# ouch_area_schematic.net
KiCad netlist of a schematic drawn in Altium Designer
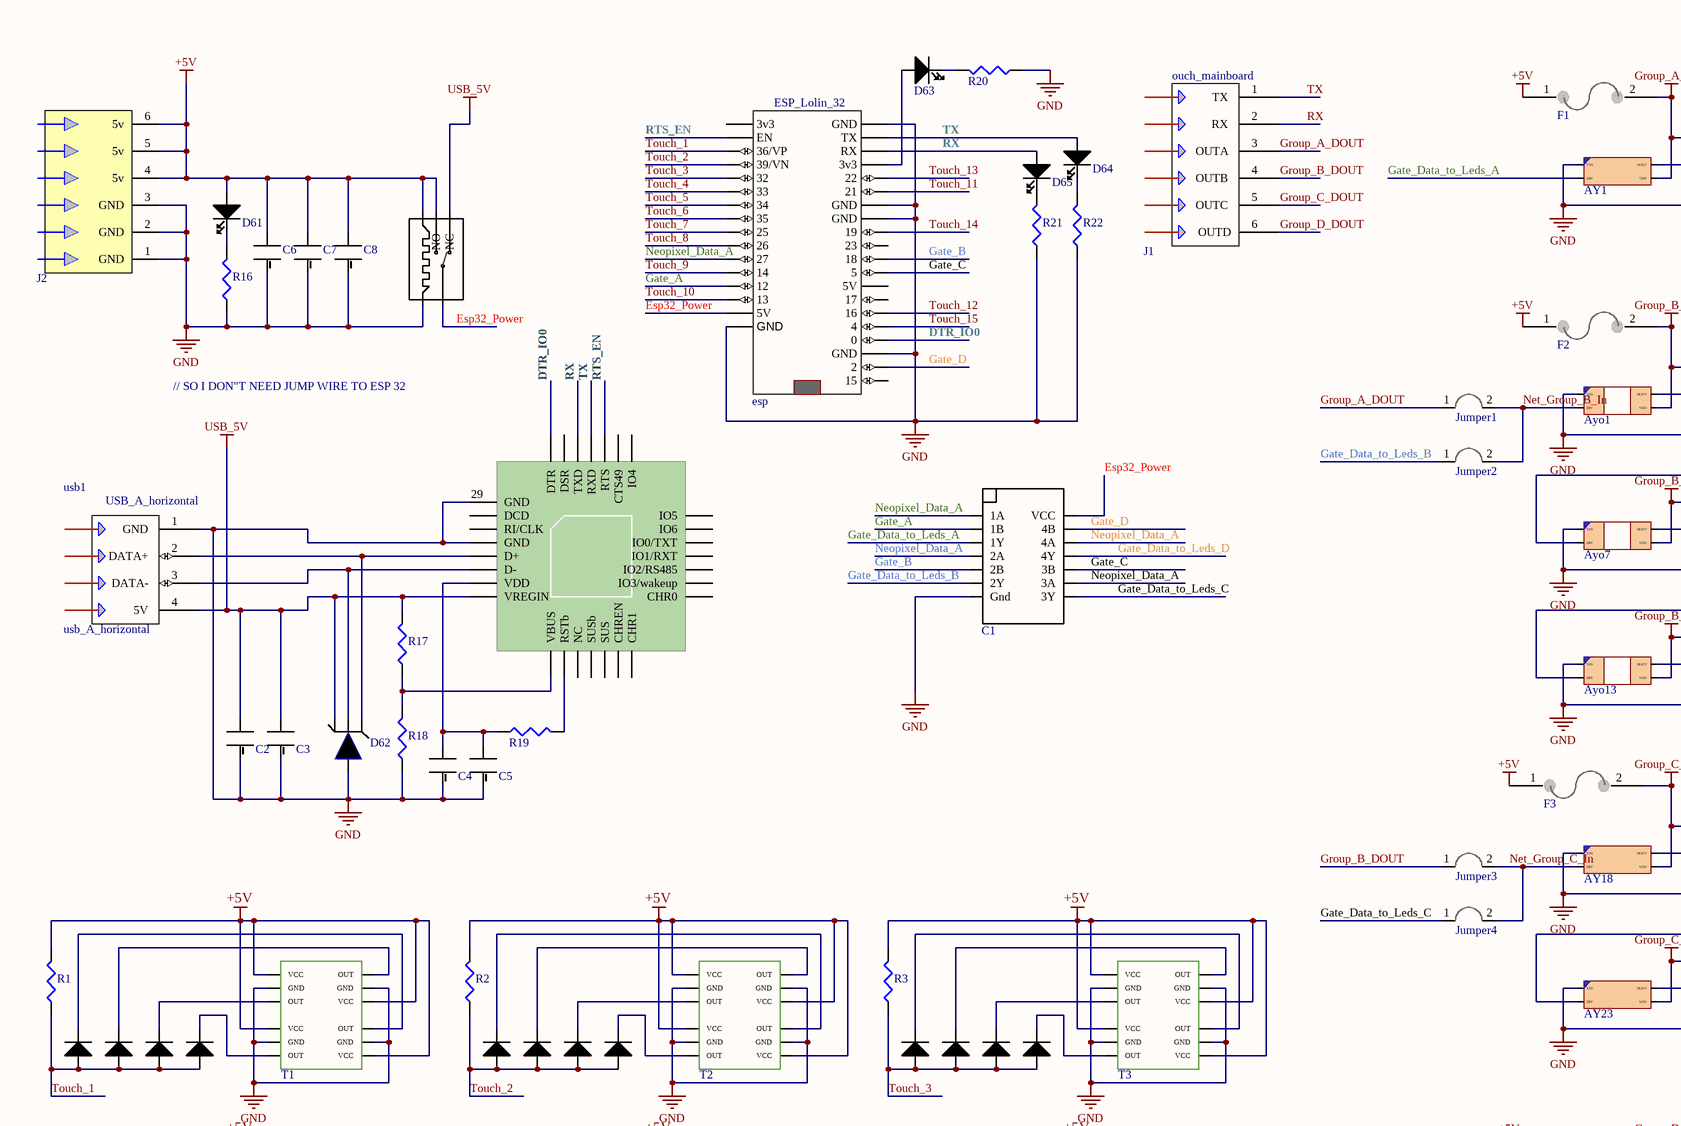
[diagram p0: ouch_area_schematic.SchDoc, top left]
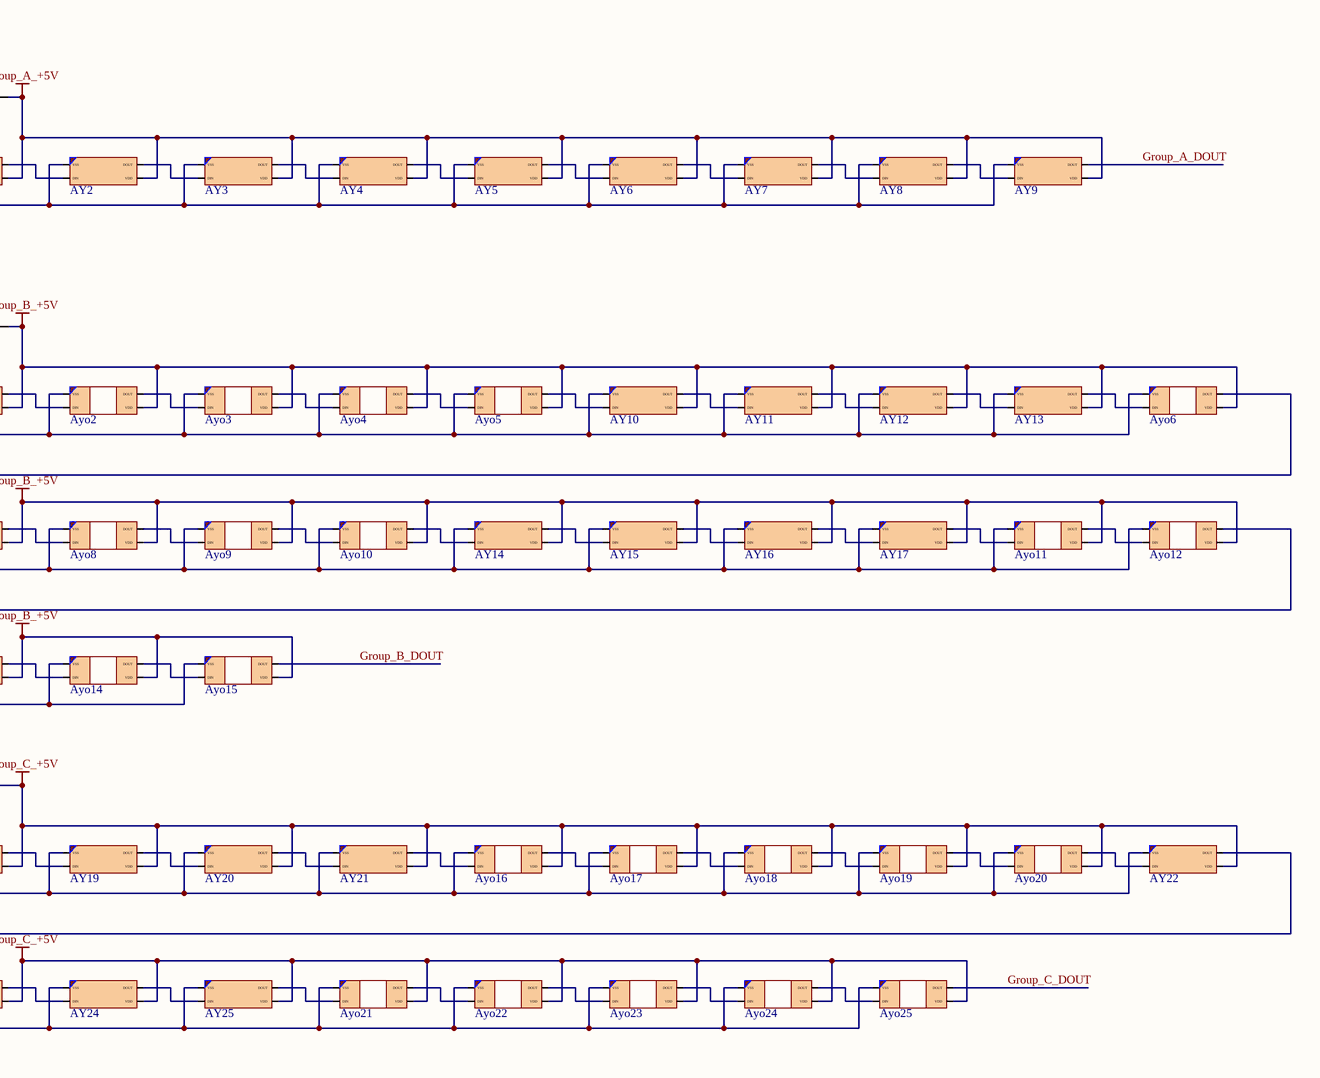
[diagram p1: ouch_area_schematic.SchDoc, top right]
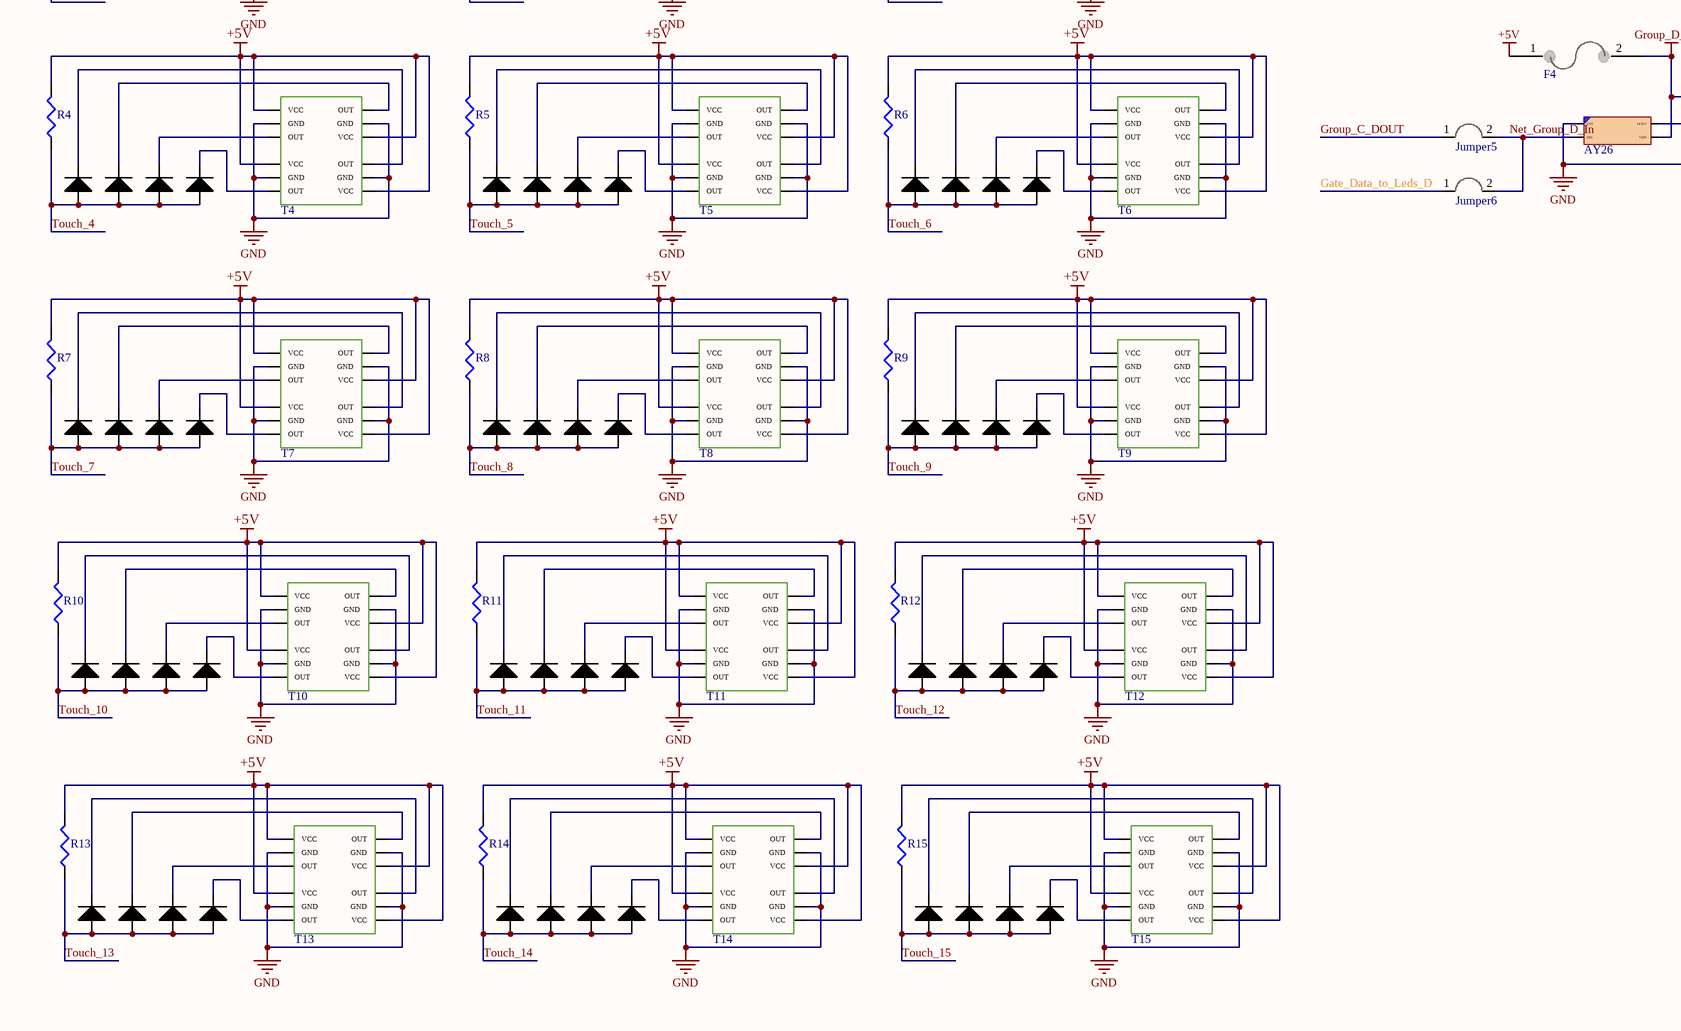
[diagram p2: ouch_area_schematic.SchDoc, bottom left]
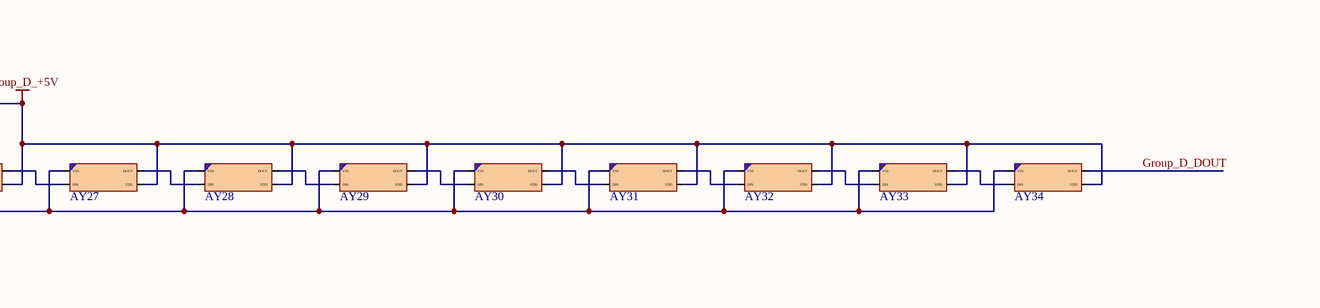
[diagram p3: ouch_area_schematic.SchDoc, bottom right]

(export (version "E")
  (design (tool "Eeschema 10.0.6"))
  (components
    (comp (ref "AY1")
      (value "1")
      (footprint "27xWs2812B_withC")
      (libsource (lib "WTFschlibra") (part "Ws2812_27leds"))
    )
    (comp (ref "AY2")
      (value "28")
      (footprint "27xWs2812B_withC")
      (libsource (lib "WTFschlibra") (part "Ws2812_27leds"))
    )
    (comp (ref "AY3")
      (value "55")
      (footprint "27xWs2812B_withC")
      (libsource (lib "WTFschlibra") (part "Ws2812_27leds"))
    )
    (comp (ref "AY4")
      (value "82")
      (footprint "27xWs2812B_withC")
      (libsource (lib "WTFschlibra") (part "Ws2812_27leds"))
    )
    (comp (ref "AY5")
      (value "109")
      (footprint "27xWs2812B_withC")
      (libsource (lib "WTFschlibra") (part "Ws2812_27leds"))
    )
    (comp (ref "AY6")
      (value "136")
      (footprint "27xWs2812B_withC")
      (libsource (lib "WTFschlibra") (part "Ws2812_27leds"))
    )
    (comp (ref "AY7")
      (value "163")
      (footprint "27xWs2812B_withC")
      (libsource (lib "WTFschlibra") (part "Ws2812_27leds"))
    )
    (comp (ref "AY8")
      (value "190")
      (footprint "27xWs2812B_withC")
      (libsource (lib "WTFschlibra") (part "Ws2812_27leds"))
    )
    (comp (ref "AY9")
      (value "217")
      (footprint "27xWs2812B_withC")
      (libsource (lib "WTFschlibra") (part "Ws2812_27leds"))
    )
    (comp (ref "AY10")
      (value "304")
      (footprint "27xWs2812B_withC")
      (libsource (lib "WTFschlibra") (part "Ws2812_27leds"))
    )
    (comp (ref "AY11")
      (value "331")
      (footprint "27xWs2812B_withC")
      (libsource (lib "WTFschlibra") (part "Ws2812_27leds"))
    )
    (comp (ref "AY12")
      (value "358")
      (footprint "27xWs2812B_withC")
      (libsource (lib "WTFschlibra") (part "Ws2812_27leds"))
    )
    (comp (ref "AY13")
      (value "385")
      (footprint "27xWs2812B_withC")
      (libsource (lib "WTFschlibra") (part "Ws2812_27leds"))
    )
    (comp (ref "AY14")
      (value "472")
      (footprint "27xWs2812B_withC")
      (libsource (lib "WTFschlibra") (part "Ws2812_27leds"))
    )
    (comp (ref "AY15")
      (value "499")
      (footprint "27xWs2812B_withC")
      (libsource (lib "WTFschlibra") (part "Ws2812_27leds"))
    )
    (comp (ref "AY16")
      (value "526")
      (footprint "27xWs2812B_withC")
      (libsource (lib "WTFschlibra") (part "Ws2812_27leds"))
    )
    (comp (ref "AY17")
      (value "553")
      (footprint "27xWs2812B_withC")
      (libsource (lib "WTFschlibra") (part "Ws2812_27leds"))
    )
    (comp (ref "AY18")
      (value "640")
      (footprint "27xWs2812B_withC")
      (libsource (lib "WTFschlibra") (part "Ws2812_27leds"))
    )
    (comp (ref "AY19")
      (value "667")
      (footprint "27xWs2812B_withC")
      (libsource (lib "WTFschlibra") (part "Ws2812_27leds"))
    )
    (comp (ref "AY20")
      (value "694")
      (footprint "27xWs2812B_withC")
      (libsource (lib "WTFschlibra") (part "Ws2812_27leds"))
    )
    (comp (ref "AY21")
      (value "721")
      (footprint "27xWs2812B_withC")
      (libsource (lib "WTFschlibra") (part "Ws2812_27leds"))
    )
    (comp (ref "AY22")
      (value "808")
      (footprint "27xWs2812B_withC")
      (libsource (lib "WTFschlibra") (part "Ws2812_27leds"))
    )
    (comp (ref "AY23")
      (value "835")
      (footprint "27xWs2812B_withC")
      (libsource (lib "WTFschlibra") (part "Ws2812_27leds"))
    )
    (comp (ref "AY24")
      (value "862")
      (footprint "27xWs2812B_withC")
      (libsource (lib "WTFschlibra") (part "Ws2812_27leds"))
    )
    (comp (ref "AY25")
      (value "889")
      (footprint "27xWs2812B_withC")
      (libsource (lib "WTFschlibra") (part "Ws2812_27leds"))
    )
    (comp (ref "AY26")
      (value "976")
      (footprint "27xWs2812B_withC")
      (libsource (lib "WTFschlibra") (part "Ws2812_27leds"))
    )
    (comp (ref "AY27")
      (value "1003")
      (footprint "27xWs2812B_withC")
      (libsource (lib "WTFschlibra") (part "Ws2812_27leds"))
    )
    (comp (ref "AY28")
      (value "1030")
      (footprint "27xWs2812B_withC")
      (libsource (lib "WTFschlibra") (part "Ws2812_27leds"))
    )
    (comp (ref "AY29")
      (value "1057")
      (footprint "27xWs2812B_withC")
      (libsource (lib "WTFschlibra") (part "Ws2812_27leds"))
    )
    (comp (ref "AY30")
      (value "1084")
      (footprint "27xWs2812B_withC")
      (libsource (lib "WTFschlibra") (part "Ws2812_27leds"))
    )
    (comp (ref "AY31")
      (value "1111")
      (footprint "27xWs2812B_withC")
      (libsource (lib "WTFschlibra") (part "Ws2812_27leds"))
    )
    (comp (ref "AY32")
      (value "1138")
      (footprint "27xWs2812B_withC")
      (libsource (lib "WTFschlibra") (part "Ws2812_27leds"))
    )
    (comp (ref "AY33")
      (value "1165")
      (footprint "27xWs2812B_withC")
      (libsource (lib "WTFschlibra") (part "Ws2812_27leds"))
    )
    (comp (ref "AY34")
      (value "1192")
      (footprint "27xWs2812B_withC")
      (libsource (lib "WTFschlibra") (part "Ws2812_27leds"))
    )
    (comp (ref "Ayo1")
      (value "244")
      (footprint "12Xws2812b_owo")
      (libsource (lib "WTFschlibra") (part "Ws2812_12ledsOwO"))
    )
    (comp (ref "Ayo2")
      (value "256")
      (footprint "12Xws2812b_owo")
      (libsource (lib "WTFschlibra") (part "Ws2812_12ledsOwO"))
    )
    (comp (ref "Ayo3")
      (value "268")
      (footprint "12Xws2812b_owo")
      (libsource (lib "WTFschlibra") (part "Ws2812_12ledsOwO"))
    )
    (comp (ref "Ayo4")
      (value "280")
      (footprint "12Xws2812b_owo")
      (libsource (lib "WTFschlibra") (part "Ws2812_12ledsOwO"))
    )
    (comp (ref "Ayo5")
      (value "292")
      (footprint "12Xws2812b_owo")
      (libsource (lib "WTFschlibra") (part "Ws2812_12ledsOwO"))
    )
    (comp (ref "Ayo6")
      (value "412")
      (footprint "12Xws2812b_owo")
      (libsource (lib "WTFschlibra") (part "Ws2812_12ledsOwO"))
    )
    (comp (ref "Ayo7")
      (value "424")
      (footprint "12Xws2812b_owo")
      (libsource (lib "WTFschlibra") (part "Ws2812_12ledsOwO"))
    )
    (comp (ref "Ayo8")
      (value "436")
      (footprint "12Xws2812b_owo")
      (libsource (lib "WTFschlibra") (part "Ws2812_12ledsOwO"))
    )
    (comp (ref "Ayo9")
      (value "448")
      (footprint "12Xws2812b_owo")
      (libsource (lib "WTFschlibra") (part "Ws2812_12ledsOwO"))
    )
    (comp (ref "Ayo10")
      (value "460")
      (footprint "12Xws2812b_owo")
      (libsource (lib "WTFschlibra") (part "Ws2812_12ledsOwO"))
    )
    (comp (ref "Ayo11")
      (value "580")
      (footprint "12Xws2812b_owo")
      (libsource (lib "WTFschlibra") (part "Ws2812_12ledsOwO"))
    )
    (comp (ref "Ayo12")
      (value "592")
      (footprint "12Xws2812b_owo")
      (libsource (lib "WTFschlibra") (part "Ws2812_12ledsOwO"))
    )
    (comp (ref "Ayo13")
      (value "604")
      (footprint "12Xws2812b_owo")
      (libsource (lib "WTFschlibra") (part "Ws2812_12ledsOwO"))
    )
    (comp (ref "Ayo14")
      (value "616")
      (footprint "12Xws2812b_owo")
      (libsource (lib "WTFschlibra") (part "Ws2812_12ledsOwO"))
    )
    (comp (ref "Ayo15")
      (value "628")
      (footprint "12Xws2812b_owo")
      (libsource (lib "WTFschlibra") (part "Ws2812_12ledsOwO"))
    )
    (comp (ref "Ayo16")
      (value "748")
      (footprint "12Xws2812b_owo")
      (libsource (lib "WTFschlibra") (part "Ws2812_12ledsOwO"))
    )
    (comp (ref "Ayo17")
      (value "760")
      (footprint "12Xws2812b_owo")
      (libsource (lib "WTFschlibra") (part "Ws2812_12ledsOwO"))
    )
    (comp (ref "Ayo18")
      (value "772")
      (footprint "12Xws2812b_owo")
      (libsource (lib "WTFschlibra") (part "Ws2812_12ledsOwO"))
    )
    (comp (ref "Ayo19")
      (value "784")
      (footprint "12Xws2812b_owo")
      (libsource (lib "WTFschlibra") (part "Ws2812_12ledsOwO"))
    )
    (comp (ref "Ayo20")
      (value "796")
      (footprint "12Xws2812b_owo")
      (libsource (lib "WTFschlibra") (part "Ws2812_12ledsOwO"))
    )
    (comp (ref "Ayo21")
      (value "916")
      (footprint "12Xws2812b_owo")
      (libsource (lib "WTFschlibra") (part "Ws2812_12ledsOwO"))
    )
    (comp (ref "Ayo22")
      (value "928")
      (footprint "12Xws2812b_owo")
      (libsource (lib "WTFschlibra") (part "Ws2812_12ledsOwO"))
    )
    (comp (ref "Ayo23")
      (value "940")
      (footprint "12Xws2812b_owo")
      (libsource (lib "WTFschlibra") (part "Ws2812_12ledsOwO"))
    )
    (comp (ref "Ayo24")
      (value "952")
      (footprint "12Xws2812b_owo")
      (libsource (lib "WTFschlibra") (part "Ws2812_12ledsOwO"))
    )
    (comp (ref "Ayo25")
      (value "964")
      (footprint "12Xws2812b_owo")
      (libsource (lib "WTFschlibra") (part "Ws2812_12ledsOwO"))
    )
    (comp (ref "C1")
      (value "74hc08d")
      (footprint "SOP14(74hc08d)")
      (libsource (lib "WTFschlibra") (part "74HC08"))
    )
    (comp (ref "C2")
      (value "C4R7")
      (footprint "Capacitor0603")
      (description "Cap Ceramic 4.7uF 6.3V X5R 20% Pad SMD 0402 85C T/R")
      (fields (field (name "TOLERANCE") "20%"))
      (libsource (lib "WTFschlibra") (part "capacitor0603"))
    )
    (comp (ref "C3")
      (value "C104")
      (footprint "Capacitor0603")
      (description "0.1uf")
      (fields (field (name "TOLERANCE") "20%"))
      (libsource (lib "WTFschlibra") (part "capacitor0603"))
    )
    (comp (ref "C4")
      (value "C104")
      (footprint "Capacitor0603")
      (description "4.7")
      (fields (field (name "TOLERANCE") "20%"))
      (libsource (lib "WTFschlibra") (part "capacitor0603"))
    )
    (comp (ref "C5")
      (value "C4R7")
      (footprint "Capacitor0603")
      (description "0.1")
      (fields (field (name "TOLERANCE") "20%"))
      (libsource (lib "WTFschlibra") (part "capacitor0603"))
    )
    (comp (ref "C6")
      (value "EEU-FM0J331")
      (footprint "2.5mmCapacitor")
      (description "Cap 330 uF;  Tol 20%;  Vol-Rtg 6.3 VDC;  Radial;  6.3x11.2;  Bulk")
      (fields (field (name "TOLERANCE") "20%") (field (name "VOLTAGE") "6.3V"))
      (libsource (lib "WTFschlibra") (part "EEU-FM0J331"))
    )
    (comp (ref "C7")
      (value "EEU-FM0J331")
      (footprint "2.5mmCapacitor")
      (description "Cap 330 uF;  Tol 20%;  Vol-Rtg 6.3 VDC;  Radial;  6.3x11.2;  Bulk")
      (fields (field (name "TOLERANCE") "20%") (field (name "VOLTAGE") "6.3V"))
      (libsource (lib "WTFschlibra") (part "EEU-FM0J331"))
    )
    (comp (ref "C8")
      (value "EEU-FM0J331")
      (footprint "2.5mmCapacitor")
      (description "Cap 330 uF;  Tol 20%;  Vol-Rtg 6.3 VDC;  Radial;  6.3x11.2;  Bulk")
      (fields (field (name "TOLERANCE") "20%") (field (name "VOLTAGE") "6.3V"))
      (libsource (lib "WTFschlibra") (part "EEU-FM0J331"))
    )
    (comp (ref "cp1")
      (value "CP2102N")
      (footprint "CP2102N_QFN28")
      (description "Full Speed USB to UART Bridge USB 2.0 3.3V T/R Automotive 28-Pin QFN EP")
      (libsource (lib "WTFschlibra") (part "CP2102N-A02-GQFN28R"))
    )
    (comp (ref "D1")
      (value "LL4148")
      (footprint "SOD80-LL4148")
      (description "ON SEMICONDUCTOR - LL4148 - Small Signal Diode, Single, 100 V, 200 mA, 1 V, 4 ns, 2 A")
      (fields (field (name "VOLTAGE") "100V"))
      (libsource (lib "WTFschlibra") (part "LL4148"))
    )
    (comp (ref "D2")
      (value "LL4148")
      (footprint "SOD80-LL4148")
      (description "ON SEMICONDUCTOR - LL4148 - Small Signal Diode, Single, 100 V, 200 mA, 1 V, 4 ns, 2 A")
      (fields (field (name "VOLTAGE") "100V"))
      (libsource (lib "WTFschlibra") (part "LL4148"))
    )
    (comp (ref "D3")
      (value "LL4148")
      (footprint "SOD80-LL4148")
      (description "ON SEMICONDUCTOR - LL4148 - Small Signal Diode, Single, 100 V, 200 mA, 1 V, 4 ns, 2 A")
      (fields (field (name "VOLTAGE") "100V"))
      (libsource (lib "WTFschlibra") (part "LL4148"))
    )
    (comp (ref "D4")
      (value "LL4148")
      (footprint "SOD80-LL4148")
      (description "ON SEMICONDUCTOR - LL4148 - Small Signal Diode, Single, 100 V, 200 mA, 1 V, 4 ns, 2 A")
      (fields (field (name "VOLTAGE") "100V"))
      (libsource (lib "WTFschlibra") (part "LL4148"))
    )
    (comp (ref "D5")
      (value "LL4148")
      (footprint "SOD80-LL4148")
      (description "ON SEMICONDUCTOR - LL4148 - Small Signal Diode, Single, 100 V, 200 mA, 1 V, 4 ns, 2 A")
      (fields (field (name "VOLTAGE") "100V"))
      (libsource (lib "WTFschlibra") (part "LL4148"))
    )
    (comp (ref "D6")
      (value "LL4148")
      (footprint "SOD80-LL4148")
      (description "ON SEMICONDUCTOR - LL4148 - Small Signal Diode, Single, 100 V, 200 mA, 1 V, 4 ns, 2 A")
      (fields (field (name "VOLTAGE") "100V"))
      (libsource (lib "WTFschlibra") (part "LL4148"))
    )
    (comp (ref "D7")
      (value "LL4148")
      (footprint "SOD80-LL4148")
      (description "ON SEMICONDUCTOR - LL4148 - Small Signal Diode, Single, 100 V, 200 mA, 1 V, 4 ns, 2 A")
      (fields (field (name "VOLTAGE") "100V"))
      (libsource (lib "WTFschlibra") (part "LL4148"))
    )
    (comp (ref "D8")
      (value "LL4148")
      (footprint "SOD80-LL4148")
      (description "ON SEMICONDUCTOR - LL4148 - Small Signal Diode, Single, 100 V, 200 mA, 1 V, 4 ns, 2 A")
      (fields (field (name "VOLTAGE") "100V"))
      (libsource (lib "WTFschlibra") (part "LL4148"))
    )
    (comp (ref "D9")
      (value "LL4148")
      (footprint "SOD80-LL4148")
      (description "ON SEMICONDUCTOR - LL4148 - Small Signal Diode, Single, 100 V, 200 mA, 1 V, 4 ns, 2 A")
      (fields (field (name "VOLTAGE") "100V"))
      (libsource (lib "WTFschlibra") (part "LL4148"))
    )
    (comp (ref "D10")
      (value "LL4148")
      (footprint "SOD80-LL4148")
      (description "ON SEMICONDUCTOR - LL4148 - Small Signal Diode, Single, 100 V, 200 mA, 1 V, 4 ns, 2 A")
      (fields (field (name "VOLTAGE") "100V"))
      (libsource (lib "WTFschlibra") (part "LL4148"))
    )
    (comp (ref "D11")
      (value "LL4148")
      (footprint "SOD80-LL4148")
      (description "ON SEMICONDUCTOR - LL4148 - Small Signal Diode, Single, 100 V, 200 mA, 1 V, 4 ns, 2 A")
      (fields (field (name "VOLTAGE") "100V"))
      (libsource (lib "WTFschlibra") (part "LL4148"))
    )
    (comp (ref "D12")
      (value "LL4148")
      (footprint "SOD80-LL4148")
      (description "ON SEMICONDUCTOR - LL4148 - Small Signal Diode, Single, 100 V, 200 mA, 1 V, 4 ns, 2 A")
      (fields (field (name "VOLTAGE") "100V"))
      (libsource (lib "WTFschlibra") (part "LL4148"))
    )
    (comp (ref "D13")
      (value "LL4148")
      (footprint "SOD80-LL4148")
      (description "ON SEMICONDUCTOR - LL4148 - Small Signal Diode, Single, 100 V, 200 mA, 1 V, 4 ns, 2 A")
      (fields (field (name "VOLTAGE") "100V"))
      (libsource (lib "WTFschlibra") (part "LL4148"))
    )
    (comp (ref "D14")
      (value "LL4148")
      (footprint "SOD80-LL4148")
      (description "ON SEMICONDUCTOR - LL4148 - Small Signal Diode, Single, 100 V, 200 mA, 1 V, 4 ns, 2 A")
      (fields (field (name "VOLTAGE") "100V"))
      (libsource (lib "WTFschlibra") (part "LL4148"))
    )
    (comp (ref "D15")
      (value "LL4148")
      (footprint "SOD80-LL4148")
      (description "ON SEMICONDUCTOR - LL4148 - Small Signal Diode, Single, 100 V, 200 mA, 1 V, 4 ns, 2 A")
      (fields (field (name "VOLTAGE") "100V"))
      (libsource (lib "WTFschlibra") (part "LL4148"))
    )
    (comp (ref "D16")
      (value "LL4148")
      (footprint "SOD80-LL4148")
      (description "ON SEMICONDUCTOR - LL4148 - Small Signal Diode, Single, 100 V, 200 mA, 1 V, 4 ns, 2 A")
      (fields (field (name "VOLTAGE") "100V"))
      (libsource (lib "WTFschlibra") (part "LL4148"))
    )
    (comp (ref "D17")
      (value "LL4148")
      (footprint "SOD80-LL4148")
      (description "ON SEMICONDUCTOR - LL4148 - Small Signal Diode, Single, 100 V, 200 mA, 1 V, 4 ns, 2 A")
      (fields (field (name "VOLTAGE") "100V"))
      (libsource (lib "WTFschlibra") (part "LL4148"))
    )
    (comp (ref "D18")
      (value "LL4148")
      (footprint "SOD80-LL4148")
      (description "ON SEMICONDUCTOR - LL4148 - Small Signal Diode, Single, 100 V, 200 mA, 1 V, 4 ns, 2 A")
      (fields (field (name "VOLTAGE") "100V"))
      (libsource (lib "WTFschlibra") (part "LL4148"))
    )
    (comp (ref "D19")
      (value "LL4148")
      (footprint "SOD80-LL4148")
      (description "ON SEMICONDUCTOR - LL4148 - Small Signal Diode, Single, 100 V, 200 mA, 1 V, 4 ns, 2 A")
      (fields (field (name "VOLTAGE") "100V"))
      (libsource (lib "WTFschlibra") (part "LL4148"))
    )
    (comp (ref "D20")
      (value "LL4148")
      (footprint "SOD80-LL4148")
      (description "ON SEMICONDUCTOR - LL4148 - Small Signal Diode, Single, 100 V, 200 mA, 1 V, 4 ns, 2 A")
      (fields (field (name "VOLTAGE") "100V"))
      (libsource (lib "WTFschlibra") (part "LL4148"))
    )
    (comp (ref "D21")
      (value "LL4148")
      (footprint "SOD80-LL4148")
      (description "ON SEMICONDUCTOR - LL4148 - Small Signal Diode, Single, 100 V, 200 mA, 1 V, 4 ns, 2 A")
      (fields (field (name "VOLTAGE") "100V"))
      (libsource (lib "WTFschlibra") (part "LL4148"))
    )
    (comp (ref "D22")
      (value "LL4148")
      (footprint "SOD80-LL4148")
      (description "ON SEMICONDUCTOR - LL4148 - Small Signal Diode, Single, 100 V, 200 mA, 1 V, 4 ns, 2 A")
      (fields (field (name "VOLTAGE") "100V"))
      (libsource (lib "WTFschlibra") (part "LL4148"))
    )
    (comp (ref "D23")
      (value "LL4148")
      (footprint "SOD80-LL4148")
      (description "ON SEMICONDUCTOR - LL4148 - Small Signal Diode, Single, 100 V, 200 mA, 1 V, 4 ns, 2 A")
      (fields (field (name "VOLTAGE") "100V"))
      (libsource (lib "WTFschlibra") (part "LL4148"))
    )
    (comp (ref "D24")
      (value "LL4148")
      (footprint "SOD80-LL4148")
      (description "ON SEMICONDUCTOR - LL4148 - Small Signal Diode, Single, 100 V, 200 mA, 1 V, 4 ns, 2 A")
      (fields (field (name "VOLTAGE") "100V"))
      (libsource (lib "WTFschlibra") (part "LL4148"))
    )
    (comp (ref "D25")
      (value "LL4148")
      (footprint "SOD80-LL4148")
      (description "ON SEMICONDUCTOR - LL4148 - Small Signal Diode, Single, 100 V, 200 mA, 1 V, 4 ns, 2 A")
      (fields (field (name "VOLTAGE") "100V"))
      (libsource (lib "WTFschlibra") (part "LL4148"))
    )
    (comp (ref "D26")
      (value "LL4148")
      (footprint "SOD80-LL4148")
      (description "ON SEMICONDUCTOR - LL4148 - Small Signal Diode, Single, 100 V, 200 mA, 1 V, 4 ns, 2 A")
      (fields (field (name "VOLTAGE") "100V"))
      (libsource (lib "WTFschlibra") (part "LL4148"))
    )
    (comp (ref "D27")
      (value "LL4148")
      (footprint "SOD80-LL4148")
      (description "ON SEMICONDUCTOR - LL4148 - Small Signal Diode, Single, 100 V, 200 mA, 1 V, 4 ns, 2 A")
      (fields (field (name "VOLTAGE") "100V"))
      (libsource (lib "WTFschlibra") (part "LL4148"))
    )
    (comp (ref "D28")
      (value "LL4148")
      (footprint "SOD80-LL4148")
      (description "ON SEMICONDUCTOR - LL4148 - Small Signal Diode, Single, 100 V, 200 mA, 1 V, 4 ns, 2 A")
      (fields (field (name "VOLTAGE") "100V"))
      (libsource (lib "WTFschlibra") (part "LL4148"))
    )
    (comp (ref "D29")
      (value "LL4148")
      (footprint "SOD80-LL4148")
      (description "ON SEMICONDUCTOR - LL4148 - Small Signal Diode, Single, 100 V, 200 mA, 1 V, 4 ns, 2 A")
      (fields (field (name "VOLTAGE") "100V"))
      (libsource (lib "WTFschlibra") (part "LL4148"))
    )
    (comp (ref "D30")
      (value "LL4148")
      (footprint "SOD80-LL4148")
      (description "ON SEMICONDUCTOR - LL4148 - Small Signal Diode, Single, 100 V, 200 mA, 1 V, 4 ns, 2 A")
      (fields (field (name "VOLTAGE") "100V"))
      (libsource (lib "WTFschlibra") (part "LL4148"))
    )
    (comp (ref "D31")
      (value "LL4148")
      (footprint "SOD80-LL4148")
      (description "ON SEMICONDUCTOR - LL4148 - Small Signal Diode, Single, 100 V, 200 mA, 1 V, 4 ns, 2 A")
      (fields (field (name "VOLTAGE") "100V"))
      (libsource (lib "WTFschlibra") (part "LL4148"))
    )
    (comp (ref "D32")
      (value "LL4148")
      (footprint "SOD80-LL4148")
      (description "ON SEMICONDUCTOR - LL4148 - Small Signal Diode, Single, 100 V, 200 mA, 1 V, 4 ns, 2 A")
      (fields (field (name "VOLTAGE") "100V"))
      (libsource (lib "WTFschlibra") (part "LL4148"))
    )
    (comp (ref "D33")
      (value "LL4148")
      (footprint "SOD80-LL4148")
      (description "ON SEMICONDUCTOR - LL4148 - Small Signal Diode, Single, 100 V, 200 mA, 1 V, 4 ns, 2 A")
      (fields (field (name "VOLTAGE") "100V"))
      (libsource (lib "WTFschlibra") (part "LL4148"))
    )
    (comp (ref "D34")
      (value "LL4148")
      (footprint "SOD80-LL4148")
      (description "ON SEMICONDUCTOR - LL4148 - Small Signal Diode, Single, 100 V, 200 mA, 1 V, 4 ns, 2 A")
      (fields (field (name "VOLTAGE") "100V"))
      (libsource (lib "WTFschlibra") (part "LL4148"))
    )
    (comp (ref "D35")
      (value "LL4148")
      (footprint "SOD80-LL4148")
      (description "ON SEMICONDUCTOR - LL4148 - Small Signal Diode, Single, 100 V, 200 mA, 1 V, 4 ns, 2 A")
      (fields (field (name "VOLTAGE") "100V"))
      (libsource (lib "WTFschlibra") (part "LL4148"))
    )
    (comp (ref "D36")
      (value "LL4148")
      (footprint "SOD80-LL4148")
      (description "ON SEMICONDUCTOR - LL4148 - Small Signal Diode, Single, 100 V, 200 mA, 1 V, 4 ns, 2 A")
      (fields (field (name "VOLTAGE") "100V"))
      (libsource (lib "WTFschlibra") (part "LL4148"))
    )
    (comp (ref "D37")
      (value "LL4148")
      (footprint "SOD80-LL4148")
      (description "ON SEMICONDUCTOR - LL4148 - Small Signal Diode, Single, 100 V, 200 mA, 1 V, 4 ns, 2 A")
      (fields (field (name "VOLTAGE") "100V"))
      (libsource (lib "WTFschlibra") (part "LL4148"))
    )
    (comp (ref "D38")
      (value "LL4148")
      (footprint "SOD80-LL4148")
      (description "ON SEMICONDUCTOR - LL4148 - Small Signal Diode, Single, 100 V, 200 mA, 1 V, 4 ns, 2 A")
      (fields (field (name "VOLTAGE") "100V"))
      (libsource (lib "WTFschlibra") (part "LL4148"))
    )
    (comp (ref "D39")
      (value "LL4148")
      (footprint "SOD80-LL4148")
      (description "ON SEMICONDUCTOR - LL4148 - Small Signal Diode, Single, 100 V, 200 mA, 1 V, 4 ns, 2 A")
      (fields (field (name "VOLTAGE") "100V"))
      (libsource (lib "WTFschlibra") (part "LL4148"))
    )
    (comp (ref "D40")
      (value "LL4148")
      (footprint "SOD80-LL4148")
      (description "ON SEMICONDUCTOR - LL4148 - Small Signal Diode, Single, 100 V, 200 mA, 1 V, 4 ns, 2 A")
      (fields (field (name "VOLTAGE") "100V"))
      (libsource (lib "WTFschlibra") (part "LL4148"))
    )
    (comp (ref "D41")
      (value "LL4148")
      (footprint "SOD80-LL4148")
      (description "ON SEMICONDUCTOR - LL4148 - Small Signal Diode, Single, 100 V, 200 mA, 1 V, 4 ns, 2 A")
      (fields (field (name "VOLTAGE") "100V"))
      (libsource (lib "WTFschlibra") (part "LL4148"))
    )
    (comp (ref "D42")
      (value "LL4148")
      (footprint "SOD80-LL4148")
      (description "ON SEMICONDUCTOR - LL4148 - Small Signal Diode, Single, 100 V, 200 mA, 1 V, 4 ns, 2 A")
      (fields (field (name "VOLTAGE") "100V"))
      (libsource (lib "WTFschlibra") (part "LL4148"))
    )
    (comp (ref "D43")
      (value "LL4148")
      (footprint "SOD80-LL4148")
      (description "ON SEMICONDUCTOR - LL4148 - Small Signal Diode, Single, 100 V, 200 mA, 1 V, 4 ns, 2 A")
      (fields (field (name "VOLTAGE") "100V"))
      (libsource (lib "WTFschlibra") (part "LL4148"))
    )
    (comp (ref "D44")
      (value "LL4148")
      (footprint "SOD80-LL4148")
      (description "ON SEMICONDUCTOR - LL4148 - Small Signal Diode, Single, 100 V, 200 mA, 1 V, 4 ns, 2 A")
      (fields (field (name "VOLTAGE") "100V"))
      (libsource (lib "WTFschlibra") (part "LL4148"))
    )
    (comp (ref "D45")
      (value "LL4148")
      (footprint "SOD80-LL4148")
      (description "ON SEMICONDUCTOR - LL4148 - Small Signal Diode, Single, 100 V, 200 mA, 1 V, 4 ns, 2 A")
      (fields (field (name "VOLTAGE") "100V"))
      (libsource (lib "WTFschlibra") (part "LL4148"))
    )
    (comp (ref "D46")
      (value "LL4148")
      (footprint "SOD80-LL4148")
      (description "ON SEMICONDUCTOR - LL4148 - Small Signal Diode, Single, 100 V, 200 mA, 1 V, 4 ns, 2 A")
      (fields (field (name "VOLTAGE") "100V"))
      (libsource (lib "WTFschlibra") (part "LL4148"))
    )
    (comp (ref "D47")
      (value "LL4148")
      (footprint "SOD80-LL4148")
      (description "ON SEMICONDUCTOR - LL4148 - Small Signal Diode, Single, 100 V, 200 mA, 1 V, 4 ns, 2 A")
      (fields (field (name "VOLTAGE") "100V"))
      (libsource (lib "WTFschlibra") (part "LL4148"))
    )
    (comp (ref "D48")
      (value "LL4148")
      (footprint "SOD80-LL4148")
      (description "ON SEMICONDUCTOR - LL4148 - Small Signal Diode, Single, 100 V, 200 mA, 1 V, 4 ns, 2 A")
      (fields (field (name "VOLTAGE") "100V"))
      (libsource (lib "WTFschlibra") (part "LL4148"))
    )
    (comp (ref "D49")
      (value "LL4148")
      (footprint "SOD80-LL4148")
      (description "ON SEMICONDUCTOR - LL4148 - Small Signal Diode, Single, 100 V, 200 mA, 1 V, 4 ns, 2 A")
      (fields (field (name "VOLTAGE") "100V"))
      (libsource (lib "WTFschlibra") (part "LL4148"))
    )
    (comp (ref "D50")
      (value "LL4148")
      (footprint "SOD80-LL4148")
      (description "ON SEMICONDUCTOR - LL4148 - Small Signal Diode, Single, 100 V, 200 mA, 1 V, 4 ns, 2 A")
      (fields (field (name "VOLTAGE") "100V"))
      (libsource (lib "WTFschlibra") (part "LL4148"))
    )
    (comp (ref "D51")
      (value "LL4148")
      (footprint "SOD80-LL4148")
      (description "ON SEMICONDUCTOR - LL4148 - Small Signal Diode, Single, 100 V, 200 mA, 1 V, 4 ns, 2 A")
      (fields (field (name "VOLTAGE") "100V"))
      (libsource (lib "WTFschlibra") (part "LL4148"))
    )
    (comp (ref "D52")
      (value "LL4148")
      (footprint "SOD80-LL4148")
      (description "ON SEMICONDUCTOR - LL4148 - Small Signal Diode, Single, 100 V, 200 mA, 1 V, 4 ns, 2 A")
      (fields (field (name "VOLTAGE") "100V"))
      (libsource (lib "WTFschlibra") (part "LL4148"))
    )
    (comp (ref "D53")
      (value "LL4148")
      (footprint "SOD80-LL4148")
      (description "ON SEMICONDUCTOR - LL4148 - Small Signal Diode, Single, 100 V, 200 mA, 1 V, 4 ns, 2 A")
      (fields (field (name "VOLTAGE") "100V"))
      (libsource (lib "WTFschlibra") (part "LL4148"))
    )
    (comp (ref "D54")
      (value "LL4148")
      (footprint "SOD80-LL4148")
      (description "ON SEMICONDUCTOR - LL4148 - Small Signal Diode, Single, 100 V, 200 mA, 1 V, 4 ns, 2 A")
      (fields (field (name "VOLTAGE") "100V"))
      (libsource (lib "WTFschlibra") (part "LL4148"))
    )
    (comp (ref "D55")
      (value "LL4148")
      (footprint "SOD80-LL4148")
      (description "ON SEMICONDUCTOR - LL4148 - Small Signal Diode, Single, 100 V, 200 mA, 1 V, 4 ns, 2 A")
      (fields (field (name "VOLTAGE") "100V"))
      (libsource (lib "WTFschlibra") (part "LL4148"))
    )
    (comp (ref "D56")
      (value "LL4148")
      (footprint "SOD80-LL4148")
      (description "ON SEMICONDUCTOR - LL4148 - Small Signal Diode, Single, 100 V, 200 mA, 1 V, 4 ns, 2 A")
      (fields (field (name "VOLTAGE") "100V"))
      (libsource (lib "WTFschlibra") (part "LL4148"))
    )
    (comp (ref "D57")
      (value "LL4148")
      (footprint "SOD80-LL4148")
      (description "ON SEMICONDUCTOR - LL4148 - Small Signal Diode, Single, 100 V, 200 mA, 1 V, 4 ns, 2 A")
      (fields (field (name "VOLTAGE") "100V"))
      (libsource (lib "WTFschlibra") (part "LL4148"))
    )
    (comp (ref "D58")
      (value "LL4148")
      (footprint "SOD80-LL4148")
      (description "ON SEMICONDUCTOR - LL4148 - Small Signal Diode, Single, 100 V, 200 mA, 1 V, 4 ns, 2 A")
      (fields (field (name "VOLTAGE") "100V"))
      (libsource (lib "WTFschlibra") (part "LL4148"))
    )
    (comp (ref "D59")
      (value "LL4148")
      (footprint "SOD80-LL4148")
      (description "ON SEMICONDUCTOR - LL4148 - Small Signal Diode, Single, 100 V, 200 mA, 1 V, 4 ns, 2 A")
      (fields (field (name "VOLTAGE") "100V"))
      (libsource (lib "WTFschlibra") (part "LL4148"))
    )
    (comp (ref "D60")
      (value "LL4148")
      (footprint "SOD80-LL4148")
      (description "ON SEMICONDUCTOR - LL4148 - Small Signal Diode, Single, 100 V, 200 mA, 1 V, 4 ns, 2 A")
      (fields (field (name "VOLTAGE") "100V"))
      (libsource (lib "WTFschlibra") (part "LL4148"))
    )
    (comp (ref "D61")
      (value "P_on")
      (footprint "LED0603")
      (description "LED BLUE CLEAR CHIP SMD")
      (libsource (lib "WTFschlibra") (part "LTST-C190TBKT"))
    )
    (comp (ref "D62")
      (value "SP0503BAHTG")
      (footprint "SP0503BAHTG - SOT143-4")
      (description "ESD Suppressor TVS 5.5V 4-Pin(3+Tab) SOT-143 T/R")
      (libsource (lib "WTFschlibra") (part "SP0503BAHTG"))
    )
    (comp (ref "D63")
      (value "ESP")
      (footprint "LED0603")
      (description "LED BLUE CLEAR CHIP SMD")
      (libsource (lib "WTFschlibra") (part "LTST-C190TBKT"))
    )
    (comp (ref "D64")
      (value "TXD")
      (footprint "LED0603")
      (description "LED BLUE CLEAR CHIP SMD")
      (libsource (lib "WTFschlibra") (part "LTST-C190TBKT"))
    )
    (comp (ref "D65")
      (value "RXD")
      (footprint "LED0603")
      (description "LED BLUE CLEAR CHIP SMD")
      (libsource (lib "WTFschlibra") (part "LTST-C190TBKT"))
    )
    (comp (ref "esp")
      (value "processor")
      (footprint "ESP_32_socket")
      (libsource (lib "WTFschlibra") (part "ESP_32_lolin"))
    )
    (comp (ref "F1")
      (value "PTC_0ZCG0260FF2C")
      (footprint "SMD_1812")
      (libsource (lib "WTFschlibra") (part "PTC_0ZCG0260FF2C"))
    )
    (comp (ref "F2")
      (value "PTC_0ZCG0260FF2C")
      (footprint "SMD_1812")
      (libsource (lib "WTFschlibra") (part "PTC_0ZCG0260FF2C"))
    )
    (comp (ref "F3")
      (value "PTC_0ZCG0260FF2C")
      (footprint "SMD_1812")
      (libsource (lib "WTFschlibra") (part "PTC_0ZCG0260FF2C"))
    )
    (comp (ref "F4")
      (value "PTC_0ZCG0260FF2C")
      (footprint "SMD_1812")
      (libsource (lib "WTFschlibra") (part "PTC_0ZCG0260FF2C"))
    )
    (comp (ref "J1")
      (value "ouch_and_mainboard_connector")
      (footprint "xh2.54 6pin")
      (libsource (lib "WTFschlibra") (part "ouch_and_mainboard_connector"))
    )
    (comp (ref "J2")
      (value "4.2mm_5v_gnd_3x3")
      (footprint "4.2MM_6pin_all_5")
      (libsource (lib "WTFschlibra") (part "4.2mm_5v_gnd_3x3"))
    )
    (comp (ref "Jumper1")
      (value "FromA")
      (footprint "0805Jumper")
      (libsource (lib "WTFschlibra") (part "0805Jumper"))
    )
    (comp (ref "Jumper2")
      (value "NewB")
      (footprint "0805Jumper")
      (libsource (lib "WTFschlibra") (part "0805Jumper"))
    )
    (comp (ref "Jumper3")
      (value "FromB")
      (footprint "0805Jumper")
      (libsource (lib "WTFschlibra") (part "0805Jumper"))
    )
    (comp (ref "Jumper4")
      (value "NewC")
      (footprint "0805Jumper")
      (libsource (lib "WTFschlibra") (part "0805Jumper"))
    )
    (comp (ref "Jumper5")
      (value "FromC")
      (footprint "0805Jumper")
      (libsource (lib "WTFschlibra") (part "0805Jumper"))
    )
    (comp (ref "Jumper6")
      (value "NewD")
      (footprint "0805Jumper")
      (libsource (lib "WTFschlibra") (part "0805Jumper"))
    )
    (comp (ref "R1")
      (value "R102")
      (footprint "R0805")
      (description "Res Thick Film 0805 360 Ohm 1% 0.125W(1/8W) ±100ppm/C Molded SMD Automotive Paper T/R")
      (fields (field (name "TOLERANCE") "1%"))
      (libsource (lib "WTFschlibra") (part "resistor(CRCW0805360RFKEA"))
    )
    (comp (ref "R2")
      (value "R102")
      (footprint "R0805")
      (description "Res Thick Film 0805 360 Ohm 1% 0.125W(1/8W) ±100ppm/C Molded SMD Automotive Paper T/R")
      (fields (field (name "TOLERANCE") "1%"))
      (libsource (lib "WTFschlibra") (part "resistor(CRCW0805360RFKEA"))
    )
    (comp (ref "R3")
      (value "R102")
      (footprint "R0805")
      (description "Res Thick Film 0805 360 Ohm 1% 0.125W(1/8W) ±100ppm/C Molded SMD Automotive Paper T/R")
      (fields (field (name "TOLERANCE") "1%"))
      (libsource (lib "WTFschlibra") (part "resistor(CRCW0805360RFKEA"))
    )
    (comp (ref "R4")
      (value "R102")
      (footprint "R0805")
      (description "Res Thick Film 0805 360 Ohm 1% 0.125W(1/8W) ±100ppm/C Molded SMD Automotive Paper T/R")
      (fields (field (name "TOLERANCE") "1%"))
      (libsource (lib "WTFschlibra") (part "resistor(CRCW0805360RFKEA"))
    )
    (comp (ref "R5")
      (value "R102")
      (footprint "R0805")
      (description "Res Thick Film 0805 360 Ohm 1% 0.125W(1/8W) ±100ppm/C Molded SMD Automotive Paper T/R")
      (fields (field (name "TOLERANCE") "1%"))
      (libsource (lib "WTFschlibra") (part "resistor(CRCW0805360RFKEA"))
    )
    (comp (ref "R6")
      (value "R102")
      (footprint "R0805")
      (description "Res Thick Film 0805 360 Ohm 1% 0.125W(1/8W) ±100ppm/C Molded SMD Automotive Paper T/R")
      (fields (field (name "TOLERANCE") "1%"))
      (libsource (lib "WTFschlibra") (part "resistor(CRCW0805360RFKEA"))
    )
    (comp (ref "R7")
      (value "R102")
      (footprint "R0805")
      (description "Res Thick Film 0805 360 Ohm 1% 0.125W(1/8W) ±100ppm/C Molded SMD Automotive Paper T/R")
      (fields (field (name "TOLERANCE") "1%"))
      (libsource (lib "WTFschlibra") (part "resistor(CRCW0805360RFKEA"))
    )
    (comp (ref "R8")
      (value "R102")
      (footprint "R0805")
      (description "Res Thick Film 0805 360 Ohm 1% 0.125W(1/8W) ±100ppm/C Molded SMD Automotive Paper T/R")
      (fields (field (name "TOLERANCE") "1%"))
      (libsource (lib "WTFschlibra") (part "resistor(CRCW0805360RFKEA"))
    )
    (comp (ref "R9")
      (value "R102")
      (footprint "R0805")
      (description "Res Thick Film 0805 360 Ohm 1% 0.125W(1/8W) ±100ppm/C Molded SMD Automotive Paper T/R")
      (fields (field (name "TOLERANCE") "1%"))
      (libsource (lib "WTFschlibra") (part "resistor(CRCW0805360RFKEA"))
    )
    (comp (ref "R10")
      (value "R102")
      (footprint "R0805")
      (description "Res Thick Film 0805 360 Ohm 1% 0.125W(1/8W) ±100ppm/C Molded SMD Automotive Paper T/R")
      (fields (field (name "TOLERANCE") "1%"))
      (libsource (lib "WTFschlibra") (part "resistor(CRCW0805360RFKEA"))
    )
    (comp (ref "R11")
      (value "R102")
      (footprint "R0805")
      (description "Res Thick Film 0805 360 Ohm 1% 0.125W(1/8W) ±100ppm/C Molded SMD Automotive Paper T/R")
      (fields (field (name "TOLERANCE") "1%"))
      (libsource (lib "WTFschlibra") (part "resistor(CRCW0805360RFKEA"))
    )
    (comp (ref "R12")
      (value "R102")
      (footprint "R0805")
      (description "Res Thick Film 0805 360 Ohm 1% 0.125W(1/8W) ±100ppm/C Molded SMD Automotive Paper T/R")
      (fields (field (name "TOLERANCE") "1%"))
      (libsource (lib "WTFschlibra") (part "resistor(CRCW0805360RFKEA"))
    )
    (comp (ref "R13")
      (value "R102")
      (footprint "R0805")
      (description "Res Thick Film 0805 360 Ohm 1% 0.125W(1/8W) ±100ppm/C Molded SMD Automotive Paper T/R")
      (fields (field (name "TOLERANCE") "1%"))
      (libsource (lib "WTFschlibra") (part "resistor(CRCW0805360RFKEA"))
    )
    (comp (ref "R14")
      (value "R102")
      (footprint "R0805")
      (description "Res Thick Film 0805 360 Ohm 1% 0.125W(1/8W) ±100ppm/C Molded SMD Automotive Paper T/R")
      (fields (field (name "TOLERANCE") "1%"))
      (libsource (lib "WTFschlibra") (part "resistor(CRCW0805360RFKEA"))
    )
    (comp (ref "R15")
      (value "R102")
      (footprint "R0805")
      (description "Res Thick Film 0805 360 Ohm 1% 0.125W(1/8W) ±100ppm/C Molded SMD Automotive Paper T/R")
      (fields (field (name "TOLERANCE") "1%"))
      (libsource (lib "WTFschlibra") (part "resistor(CRCW0805360RFKEA"))
    )
    (comp (ref "R16")
      (value "R360")
      (footprint "R0805")
      (description "Res Thick Film 0805 360 Ohm 1% 0.125W(1/8W) ±100ppm/C Molded SMD Automotive Paper T/R")
      (fields (field (name "TOLERANCE") "1%"))
      (libsource (lib "WTFschlibra") (part "CRCW0805360RFKEA"))
    )
    (comp (ref "R17")
      (value "R2212")
      (footprint "R0805")
      (description "Res Thick Film 0805 360 Ohm 1% 0.125W(1/8W) ±100ppm/C Molded SMD Automotive Paper T/R")
      (fields (field (name "TOLERANCE") "1%"))
      (libsource (lib "WTFschlibra") (part "resistor(CRCW0805360RFKEA"))
    )
    (comp (ref "R18")
      (value "R4752")
      (footprint "R0805")
      (description "Res Thick Film 0805 360 Ohm 1% 0.125W(1/8W) ±100ppm/C Molded SMD Automotive Paper T/R")
      (fields (field (name "TOLERANCE") "1%"))
      (libsource (lib "WTFschlibra") (part "resistor(CRCW0805360RFKEA"))
    )
    (comp (ref "R19")
      (value "R102")
      (footprint "R0805")
      (description "1Kohms")
      (fields (field (name "TOLERANCE") "1%"))
      (libsource (lib "WTFschlibra") (part "resistor(CRCW0805360RFKEA"))
    )
    (comp (ref "R20")
      (value "360R")
      (footprint "R0805")
      (description "Res Thick Film 0805 360 Ohm 1% 0.125W(1/8W) ±100ppm/C Molded SMD Automotive Paper T/R")
      (fields (field (name "TOLERANCE") "1%"))
      (libsource (lib "WTFschlibra") (part "CRCW0805360RFKEA"))
    )
    (comp (ref "R21")
      (value "R360")
      (footprint "R0805")
      (description "Res Thick Film 0805 360 Ohm 1% 0.125W(1/8W) ±100ppm/C Molded SMD Automotive Paper T/R")
      (fields (field (name "TOLERANCE") "1%"))
      (libsource (lib "WTFschlibra") (part "CRCW0805360RFKEA"))
    )
    (comp (ref "R22")
      (value "R360")
      (footprint "R0805")
      (description "Res Thick Film 0805 360 Ohm 1% 0.125W(1/8W) ±100ppm/C Molded SMD Automotive Paper T/R")
      (fields (field (name "TOLERANCE") "1%"))
      (libsource (lib "WTFschlibra") (part "CRCW0805360RFKEA"))
    )
    (comp (ref "Relay1")
      (value "Omron_G5v_dc5")
      (footprint "G5v1_5vdc")
      (libsource (lib "WTFschlibra") (part "Omron_G5v_dc5"))
    )
    (comp (ref "T1")
      (value "Touch_pads2x2")
      (footprint "TouchBoard2x2")
      (libsource (lib "WTFschlibra") (part "Touch_pads2x2"))
    )
    (comp (ref "T2")
      (value "Touch_pads2x2")
      (footprint "TouchBoard2x2")
      (libsource (lib "WTFschlibra") (part "Touch_pads2x2"))
    )
    (comp (ref "T3")
      (value "Touch_pads2x2")
      (footprint "TouchBoard2x2")
      (libsource (lib "WTFschlibra") (part "Touch_pads2x2"))
    )
    (comp (ref "T4")
      (value "Touch_pads2x2")
      (footprint "TouchBoard2x2")
      (libsource (lib "WTFschlibra") (part "Touch_pads2x2"))
    )
    (comp (ref "T5")
      (value "Touch_pads2x2")
      (footprint "TouchBoard2x2")
      (libsource (lib "WTFschlibra") (part "Touch_pads2x2"))
    )
    (comp (ref "T6")
      (value "Touch_pads2x2")
      (footprint "TouchBoard2x2")
      (libsource (lib "WTFschlibra") (part "Touch_pads2x2"))
    )
    (comp (ref "T7")
      (value "Touch_pads2x2")
      (footprint "TouchBoard2x2")
      (libsource (lib "WTFschlibra") (part "Touch_pads2x2"))
    )
    (comp (ref "T8")
      (value "Touch_pads2x2")
      (footprint "TouchBoard2x2")
      (libsource (lib "WTFschlibra") (part "Touch_pads2x2"))
    )
    (comp (ref "T9")
      (value "Touch_pads2x2")
      (footprint "TouchBoard2x2")
      (libsource (lib "WTFschlibra") (part "Touch_pads2x2"))
    )
    (comp (ref "T10")
      (value "Touch_pads2x2")
      (footprint "TouchBoard2x2")
      (libsource (lib "WTFschlibra") (part "Touch_pads2x2"))
    )
    (comp (ref "T11")
      (value "Touch_pads2x2")
      (footprint "TouchBoard2x2")
      (libsource (lib "WTFschlibra") (part "Touch_pads2x2"))
    )
    (comp (ref "T12")
      (value "Touch_pads2x2")
      (footprint "TouchBoard2x2")
      (libsource (lib "WTFschlibra") (part "Touch_pads2x2"))
    )
    (comp (ref "T13")
      (value "Touch_pads2x2")
      (footprint "TouchBoard2x2")
      (libsource (lib "WTFschlibra") (part "Touch_pads2x2"))
    )
    (comp (ref "T14")
      (value "Touch_pads2x2")
      (footprint "TouchBoard2x2")
      (libsource (lib "WTFschlibra") (part "Touch_pads2x2"))
    )
    (comp (ref "T15")
      (value "Touch_pads2x2")
      (footprint "TouchBoard2x2")
      (libsource (lib "WTFschlibra") (part "Touch_pads2x2"))
    )
    (comp (ref "usb1")
      (value "usb_A_horizontal")
      (footprint "USBA_male_socket")
      (description "4 Position Single Port Socket Right Angle Type A Through Hole USB")
      (libsource (lib "WTFschlibra") (part "usb_A_horizontal"))
    )
  )
  (nets
    (net (code "1") (name "+5V") (class "Default")
      (node (ref "C6") (pin "2") (pinfunction "+_2") (pintype "passive"))
      (node (ref "C7") (pin "2") (pinfunction "+_2") (pintype "passive"))
      (node (ref "C8") (pin "2") (pinfunction "+_2") (pintype "passive"))
      (node (ref "D61") (pin "2") (pinfunction "2_2") (pintype "passive"))
      (node (ref "F1") (pin "1") (pinfunction "1_1") (pintype "passive"))
      (node (ref "F2") (pin "1") (pinfunction "1_1") (pintype "passive"))
      (node (ref "F3") (pin "1") (pinfunction "1_1") (pintype "passive"))
      (node (ref "F4") (pin "1") (pinfunction "1_1") (pintype "passive"))
      (node (ref "J2") (pin "4") (pinfunction "5v_4") (pintype "power_in"))
      (node (ref "J2") (pin "5") (pinfunction "5v_5") (pintype "power_in"))
      (node (ref "J2") (pin "6") (pinfunction "5v_6") (pintype "power_in"))
      (node (ref "R1") (pin "2") (pinfunction "2_2") (pintype "passive"))
      (node (ref "R10") (pin "2") (pinfunction "2_2") (pintype "passive"))
      (node (ref "R11") (pin "2") (pinfunction "2_2") (pintype "passive"))
      (node (ref "R12") (pin "2") (pinfunction "2_2") (pintype "passive"))
      (node (ref "R13") (pin "2") (pinfunction "2_2") (pintype "passive"))
      (node (ref "R14") (pin "2") (pinfunction "2_2") (pintype "passive"))
      (node (ref "R15") (pin "2") (pinfunction "2_2") (pintype "passive"))
      (node (ref "R2") (pin "2") (pinfunction "2_2") (pintype "passive"))
      (node (ref "R3") (pin "2") (pinfunction "2_2") (pintype "passive"))
      (node (ref "R4") (pin "2") (pinfunction "2_2") (pintype "passive"))
      (node (ref "R5") (pin "2") (pinfunction "2_2") (pintype "passive"))
      (node (ref "R6") (pin "2") (pinfunction "2_2") (pintype "passive"))
      (node (ref "R7") (pin "2") (pinfunction "2_2") (pintype "passive"))
      (node (ref "R8") (pin "2") (pinfunction "2_2") (pintype "passive"))
      (node (ref "R9") (pin "2") (pinfunction "2_2") (pintype "passive"))
      (node (ref "Relay1") (pin "1") (pinfunction "Coli_A_1") (pintype "passive"))
      (node (ref "Relay1") (pin "5") (pinfunction "NO_5") (pintype "passive"))
      (node (ref "T1") (pin "1") (pinfunction "VCC_1") (pintype "passive"))
      (node (ref "T1") (pin "10") (pinfunction "VCC_10") (pintype "passive"))
      (node (ref "T1") (pin "4") (pinfunction "VCC_4") (pintype "passive"))
      (node (ref "T1") (pin "7") (pinfunction "VCC_7") (pintype "passive"))
      (node (ref "T10") (pin "1") (pinfunction "VCC_1") (pintype "passive"))
      (node (ref "T10") (pin "10") (pinfunction "VCC_10") (pintype "passive"))
      (node (ref "T10") (pin "4") (pinfunction "VCC_4") (pintype "passive"))
      (node (ref "T10") (pin "7") (pinfunction "VCC_7") (pintype "passive"))
      (node (ref "T11") (pin "1") (pinfunction "VCC_1") (pintype "passive"))
      (node (ref "T11") (pin "10") (pinfunction "VCC_10") (pintype "passive"))
      (node (ref "T11") (pin "4") (pinfunction "VCC_4") (pintype "passive"))
      (node (ref "T11") (pin "7") (pinfunction "VCC_7") (pintype "passive"))
      (node (ref "T12") (pin "1") (pinfunction "VCC_1") (pintype "passive"))
      (node (ref "T12") (pin "10") (pinfunction "VCC_10") (pintype "passive"))
      (node (ref "T12") (pin "4") (pinfunction "VCC_4") (pintype "passive"))
      (node (ref "T12") (pin "7") (pinfunction "VCC_7") (pintype "passive"))
      (node (ref "T13") (pin "1") (pinfunction "VCC_1") (pintype "passive"))
      (node (ref "T13") (pin "10") (pinfunction "VCC_10") (pintype "passive"))
      (node (ref "T13") (pin "4") (pinfunction "VCC_4") (pintype "passive"))
      (node (ref "T13") (pin "7") (pinfunction "VCC_7") (pintype "passive"))
      (node (ref "T14") (pin "1") (pinfunction "VCC_1") (pintype "passive"))
      (node (ref "T14") (pin "10") (pinfunction "VCC_10") (pintype "passive"))
      (node (ref "T14") (pin "4") (pinfunction "VCC_4") (pintype "passive"))
      (node (ref "T14") (pin "7") (pinfunction "VCC_7") (pintype "passive"))
      (node (ref "T15") (pin "1") (pinfunction "VCC_1") (pintype "passive"))
      (node (ref "T15") (pin "10") (pinfunction "VCC_10") (pintype "passive"))
      (node (ref "T15") (pin "4") (pinfunction "VCC_4") (pintype "passive"))
      (node (ref "T15") (pin "7") (pinfunction "VCC_7") (pintype "passive"))
      (node (ref "T2") (pin "1") (pinfunction "VCC_1") (pintype "passive"))
      (node (ref "T2") (pin "10") (pinfunction "VCC_10") (pintype "passive"))
      (node (ref "T2") (pin "4") (pinfunction "VCC_4") (pintype "passive"))
      (node (ref "T2") (pin "7") (pinfunction "VCC_7") (pintype "passive"))
      (node (ref "T3") (pin "1") (pinfunction "VCC_1") (pintype "passive"))
      (node (ref "T3") (pin "10") (pinfunction "VCC_10") (pintype "passive"))
      (node (ref "T3") (pin "4") (pinfunction "VCC_4") (pintype "passive"))
      (node (ref "T3") (pin "7") (pinfunction "VCC_7") (pintype "passive"))
      (node (ref "T4") (pin "1") (pinfunction "VCC_1") (pintype "passive"))
      (node (ref "T4") (pin "10") (pinfunction "VCC_10") (pintype "passive"))
      (node (ref "T4") (pin "4") (pinfunction "VCC_4") (pintype "passive"))
      (node (ref "T4") (pin "7") (pinfunction "VCC_7") (pintype "passive"))
      (node (ref "T5") (pin "1") (pinfunction "VCC_1") (pintype "passive"))
      (node (ref "T5") (pin "10") (pinfunction "VCC_10") (pintype "passive"))
      (node (ref "T5") (pin "4") (pinfunction "VCC_4") (pintype "passive"))
      (node (ref "T5") (pin "7") (pinfunction "VCC_7") (pintype "passive"))
      (node (ref "T6") (pin "1") (pinfunction "VCC_1") (pintype "passive"))
      (node (ref "T6") (pin "10") (pinfunction "VCC_10") (pintype "passive"))
      (node (ref "T6") (pin "4") (pinfunction "VCC_4") (pintype "passive"))
      (node (ref "T6") (pin "7") (pinfunction "VCC_7") (pintype "passive"))
      (node (ref "T7") (pin "1") (pinfunction "VCC_1") (pintype "passive"))
      (node (ref "T7") (pin "10") (pinfunction "VCC_10") (pintype "passive"))
      (node (ref "T7") (pin "4") (pinfunction "VCC_4") (pintype "passive"))
      (node (ref "T7") (pin "7") (pinfunction "VCC_7") (pintype "passive"))
      (node (ref "T8") (pin "1") (pinfunction "VCC_1") (pintype "passive"))
      (node (ref "T8") (pin "10") (pinfunction "VCC_10") (pintype "passive"))
      (node (ref "T8") (pin "4") (pinfunction "VCC_4") (pintype "passive"))
      (node (ref "T8") (pin "7") (pinfunction "VCC_7") (pintype "passive"))
      (node (ref "T9") (pin "1") (pinfunction "VCC_1") (pintype "passive"))
      (node (ref "T9") (pin "10") (pinfunction "VCC_10") (pintype "passive"))
      (node (ref "T9") (pin "4") (pinfunction "VCC_4") (pintype "passive"))
      (node (ref "T9") (pin "7") (pinfunction "VCC_7") (pintype "passive"))
    )
    (net (code "2") (name "/DTR_IO0") (class "Default")
      (node (ref "cp1") (pin "28") (pinfunction "DTR_28") (pintype "passive"))
      (node (ref "esp") (pin "17") (pinfunction "0_17") (pintype "bidirectional"))
    )
    (net (code "3") (name "/Esp32_Power") (class "Default")
      (node (ref "C1") (pin "14") (pinfunction "VCC_14") (pintype "passive"))
      (node (ref "Relay1") (pin "3") (pinfunction "COM_3") (pintype "passive"))
      (node (ref "esp") (pin "35") (pinfunction "5V_35") (pintype "power_in"))
    )
    (net (code "4") (name "/Gate_A") (class "Default")
      (node (ref "C1") (pin "2") (pinfunction "1B_2") (pintype "passive"))
      (node (ref "esp") (pin "33") (pinfunction "12_33") (pintype "bidirectional"))
    )
    (net (code "5") (name "/Gate_B") (class "Default")
      (node (ref "C1") (pin "5") (pinfunction "2B_5") (pintype "passive"))
      (node (ref "esp") (pin "11") (pinfunction "18_11") (pintype "bidirectional"))
    )
    (net (code "6") (name "/Gate_C") (class "Default")
      (node (ref "C1") (pin "10") (pinfunction "3B_10") (pintype "passive"))
      (node (ref "esp") (pin "12") (pinfunction "5_12") (pintype "bidirectional"))
    )
    (net (code "7") (name "/Gate_D") (class "Default")
      (node (ref "C1") (pin "13") (pinfunction "4B_13") (pintype "passive"))
      (node (ref "esp") (pin "19") (pinfunction "2_19") (pintype "bidirectional"))
    )
    (net (code "8") (name "/Gate_Data_to_Leds_A") (class "Default")
      (node (ref "AY1") (pin "4") (pinfunction "DIN_4") (pintype "passive"))
      (node (ref "C1") (pin "3") (pinfunction "1Y_3") (pintype "passive"))
    )
    (net (code "9") (name "/Gate_Data_to_Leds_B") (class "Default")
      (node (ref "C1") (pin "6") (pinfunction "2Y_6") (pintype "passive"))
      (node (ref "Jumper2") (pin "1") (pinfunction "1_1") (pintype "passive"))
    )
    (net (code "10") (name "/Gate_Data_to_Leds_C") (class "Default")
      (node (ref "C1") (pin "8") (pinfunction "3Y_8") (pintype "passive"))
      (node (ref "Jumper4") (pin "1") (pinfunction "1_1") (pintype "passive"))
    )
    (net (code "11") (name "/Gate_Data_to_Leds_D") (class "Default")
      (node (ref "C1") (pin "11") (pinfunction "4Y_11") (pintype "passive"))
      (node (ref "Jumper6") (pin "1") (pinfunction "1_1") (pintype "passive"))
    )
    (net (code "12") (name "/Group_A_DOUT") (class "Default")
      (node (ref "AY9") (pin "2") (pinfunction "DOUT_2") (pintype "passive"))
      (node (ref "J1") (pin "3") (pinfunction "OUTA_3") (pintype "passive"))
      (node (ref "Jumper1") (pin "1") (pinfunction "1_1") (pintype "passive"))
    )
    (net (code "13") (name "/Group_B_DOUT") (class "Default")
      (node (ref "Ayo15") (pin "2") (pinfunction "DOUT_2") (pintype "passive"))
      (node (ref "J1") (pin "4") (pinfunction "OUTB_4") (pintype "passive"))
      (node (ref "Jumper3") (pin "1") (pinfunction "1_1") (pintype "passive"))
    )
    (net (code "14") (name "/Group_C_DOUT") (class "Default")
      (node (ref "Ayo25") (pin "2") (pinfunction "DOUT_2") (pintype "passive"))
      (node (ref "J1") (pin "5") (pinfunction "OUTC_5") (pintype "passive"))
      (node (ref "Jumper5") (pin "1") (pinfunction "1_1") (pintype "passive"))
    )
    (net (code "15") (name "/Group_D_DOUT") (class "Default")
      (node (ref "AY34") (pin "2") (pinfunction "DOUT_2") (pintype "passive"))
      (node (ref "J1") (pin "6") (pinfunction "OUTD_6") (pintype "passive"))
    )
    (net (code "16") (name "/Neopixel_Data_A") (class "Default")
      (node (ref "C1") (pin "1") (pinfunction "1A_1") (pintype "passive"))
      (node (ref "C1") (pin "12") (pinfunction "4A_12") (pintype "passive"))
      (node (ref "C1") (pin "4") (pinfunction "2A_4") (pintype "passive"))
      (node (ref "C1") (pin "9") (pinfunction "3A_9") (pintype "passive"))
      (node (ref "esp") (pin "31") (pinfunction "27_31") (pintype "bidirectional"))
    )
    (net (code "17") (name "/Net_Group_B_In") (class "Default")
      (node (ref "Ayo1") (pin "4") (pinfunction "DIN_4") (pintype "passive"))
      (node (ref "Jumper1") (pin "2") (pinfunction "2_2") (pintype "passive"))
      (node (ref "Jumper2") (pin "2") (pinfunction "2_2") (pintype "passive"))
    )
    (net (code "18") (name "/Net_Group_C_In") (class "Default")
      (node (ref "AY18") (pin "4") (pinfunction "DIN_4") (pintype "passive"))
      (node (ref "Jumper3") (pin "2") (pinfunction "2_2") (pintype "passive"))
      (node (ref "Jumper4") (pin "2") (pinfunction "2_2") (pintype "passive"))
    )
    (net (code "19") (name "/Net_Group_D_In") (class "Default")
      (node (ref "AY26") (pin "4") (pinfunction "DIN_4") (pintype "passive"))
      (node (ref "Jumper5") (pin "2") (pinfunction "2_2") (pintype "passive"))
      (node (ref "Jumper6") (pin "2") (pinfunction "2_2") (pintype "passive"))
    )
    (net (code "20") (name "/RTS_EN") (class "Default")
      (node (ref "cp1") (pin "24") (pinfunction "RTS_24") (pintype "passive"))
      (node (ref "esp") (pin "22") (pinfunction "EN_22") (pintype "passive"))
    )
    (net (code "21") (name "/RX") (class "Default")
      (node (ref "D65") (pin "2") (pinfunction "2_2") (pintype "passive"))
      (node (ref "J1") (pin "2") (pinfunction "RX_2") (pintype "passive"))
      (node (ref "cp1") (pin "26") (pinfunction "TXD_26") (pintype "passive"))
      (node (ref "esp") (pin "3") (pinfunction "RX_3") (pintype "passive"))
    )
    (net (code "22") (name "/TX") (class "Default")
      (node (ref "D64") (pin "2") (pinfunction "2_2") (pintype "passive"))
      (node (ref "J1") (pin "1") (pinfunction "TX_1") (pintype "passive"))
      (node (ref "cp1") (pin "25") (pinfunction "RXD_25") (pintype "passive"))
      (node (ref "esp") (pin "2") (pinfunction "TX_2") (pintype "passive"))
    )
    (net (code "23") (name "/Touch_1") (class "Default")
      (node (ref "D1") (pin "2") (pinfunction "2_2") (pintype "passive"))
      (node (ref "D2") (pin "2") (pinfunction "2_2") (pintype "passive"))
      (node (ref "D3") (pin "2") (pinfunction "2_2") (pintype "passive"))
      (node (ref "D4") (pin "2") (pinfunction "2_2") (pintype "passive"))
      (node (ref "R1") (pin "1") (pinfunction "1_1") (pintype "passive"))
      (node (ref "esp") (pin "23") (pinfunction "36/VP_23") (pintype "bidirectional"))
    )
    (net (code "24") (name "/Touch_2") (class "Default")
      (node (ref "D5") (pin "2") (pinfunction "2_2") (pintype "passive"))
      (node (ref "D6") (pin "2") (pinfunction "2_2") (pintype "passive"))
      (node (ref "D7") (pin "2") (pinfunction "2_2") (pintype "passive"))
      (node (ref "D8") (pin "2") (pinfunction "2_2") (pintype "passive"))
      (node (ref "R2") (pin "1") (pinfunction "1_1") (pintype "passive"))
      (node (ref "esp") (pin "24") (pinfunction "39/VN_24") (pintype "bidirectional"))
    )
    (net (code "25") (name "/Touch_3") (class "Default")
      (node (ref "D10") (pin "2") (pinfunction "2_2") (pintype "passive"))
      (node (ref "D11") (pin "2") (pinfunction "2_2") (pintype "passive"))
      (node (ref "D12") (pin "2") (pinfunction "2_2") (pintype "passive"))
      (node (ref "D9") (pin "2") (pinfunction "2_2") (pintype "passive"))
      (node (ref "R3") (pin "1") (pinfunction "1_1") (pintype "passive"))
      (node (ref "esp") (pin "25") (pinfunction "32_25") (pintype "bidirectional"))
    )
    (net (code "26") (name "/Touch_4") (class "Default")
      (node (ref "D13") (pin "2") (pinfunction "2_2") (pintype "passive"))
      (node (ref "D14") (pin "2") (pinfunction "2_2") (pintype "passive"))
      (node (ref "D15") (pin "2") (pinfunction "2_2") (pintype "passive"))
      (node (ref "D16") (pin "2") (pinfunction "2_2") (pintype "passive"))
      (node (ref "R4") (pin "1") (pinfunction "1_1") (pintype "passive"))
      (node (ref "esp") (pin "26") (pinfunction "33_26") (pintype "bidirectional"))
    )
    (net (code "27") (name "/Touch_5") (class "Default")
      (node (ref "D17") (pin "2") (pinfunction "2_2") (pintype "passive"))
      (node (ref "D18") (pin "2") (pinfunction "2_2") (pintype "passive"))
      (node (ref "D19") (pin "2") (pinfunction "2_2") (pintype "passive"))
      (node (ref "D20") (pin "2") (pinfunction "2_2") (pintype "passive"))
      (node (ref "R5") (pin "1") (pinfunction "1_1") (pintype "passive"))
      (node (ref "esp") (pin "27") (pinfunction "34_27") (pintype "bidirectional"))
    )
    (net (code "28") (name "/Touch_6") (class "Default")
      (node (ref "D21") (pin "2") (pinfunction "2_2") (pintype "passive"))
      (node (ref "D22") (pin "2") (pinfunction "2_2") (pintype "passive"))
      (node (ref "D23") (pin "2") (pinfunction "2_2") (pintype "passive"))
      (node (ref "D24") (pin "2") (pinfunction "2_2") (pintype "passive"))
      (node (ref "R6") (pin "1") (pinfunction "1_1") (pintype "passive"))
      (node (ref "esp") (pin "28") (pinfunction "35_28") (pintype "bidirectional"))
    )
    (net (code "29") (name "/Touch_7") (class "Default")
      (node (ref "D25") (pin "2") (pinfunction "2_2") (pintype "passive"))
      (node (ref "D26") (pin "2") (pinfunction "2_2") (pintype "passive"))
      (node (ref "D27") (pin "2") (pinfunction "2_2") (pintype "passive"))
      (node (ref "D28") (pin "2") (pinfunction "2_2") (pintype "passive"))
      (node (ref "R7") (pin "1") (pinfunction "1_1") (pintype "passive"))
      (node (ref "esp") (pin "29") (pinfunction "25_29") (pintype "bidirectional"))
    )
    (net (code "30") (name "/Touch_8") (class "Default")
      (node (ref "D29") (pin "2") (pinfunction "2_2") (pintype "passive"))
      (node (ref "D30") (pin "2") (pinfunction "2_2") (pintype "passive"))
      (node (ref "D31") (pin "2") (pinfunction "2_2") (pintype "passive"))
      (node (ref "D32") (pin "2") (pinfunction "2_2") (pintype "passive"))
      (node (ref "R8") (pin "1") (pinfunction "1_1") (pintype "passive"))
      (node (ref "esp") (pin "30") (pinfunction "26_30") (pintype "bidirectional"))
    )
    (net (code "31") (name "/Touch_9") (class "Default")
      (node (ref "D33") (pin "2") (pinfunction "2_2") (pintype "passive"))
      (node (ref "D34") (pin "2") (pinfunction "2_2") (pintype "passive"))
      (node (ref "D35") (pin "2") (pinfunction "2_2") (pintype "passive"))
      (node (ref "D36") (pin "2") (pinfunction "2_2") (pintype "passive"))
      (node (ref "R9") (pin "1") (pinfunction "1_1") (pintype "passive"))
      (node (ref "esp") (pin "32") (pinfunction "14_32") (pintype "bidirectional"))
    )
    (net (code "32") (name "/Touch_10") (class "Default")
      (node (ref "D37") (pin "2") (pinfunction "2_2") (pintype "passive"))
      (node (ref "D38") (pin "2") (pinfunction "2_2") (pintype "passive"))
      (node (ref "D39") (pin "2") (pinfunction "2_2") (pintype "passive"))
      (node (ref "D40") (pin "2") (pinfunction "2_2") (pintype "passive"))
      (node (ref "R10") (pin "1") (pinfunction "1_1") (pintype "passive"))
      (node (ref "esp") (pin "34") (pinfunction "13_34") (pintype "bidirectional"))
    )
    (net (code "33") (name "/Touch_11") (class "Default")
      (node (ref "D41") (pin "2") (pinfunction "2_2") (pintype "passive"))
      (node (ref "D42") (pin "2") (pinfunction "2_2") (pintype "passive"))
      (node (ref "D43") (pin "2") (pinfunction "2_2") (pintype "passive"))
      (node (ref "D44") (pin "2") (pinfunction "2_2") (pintype "passive"))
      (node (ref "R11") (pin "1") (pinfunction "1_1") (pintype "passive"))
      (node (ref "esp") (pin "6") (pinfunction "21_6") (pintype "bidirectional"))
    )
    (net (code "34") (name "/Touch_12") (class "Default")
      (node (ref "D45") (pin "2") (pinfunction "2_2") (pintype "passive"))
      (node (ref "D46") (pin "2") (pinfunction "2_2") (pintype "passive"))
      (node (ref "D47") (pin "2") (pinfunction "2_2") (pintype "passive"))
      (node (ref "D48") (pin "2") (pinfunction "2_2") (pintype "passive"))
      (node (ref "R12") (pin "1") (pinfunction "1_1") (pintype "passive"))
      (node (ref "esp") (pin "15") (pinfunction "16_15") (pintype "bidirectional"))
    )
    (net (code "35") (name "/Touch_13") (class "Default")
      (node (ref "D49") (pin "2") (pinfunction "2_2") (pintype "passive"))
      (node (ref "D50") (pin "2") (pinfunction "2_2") (pintype "passive"))
      (node (ref "D51") (pin "2") (pinfunction "2_2") (pintype "passive"))
      (node (ref "D52") (pin "2") (pinfunction "2_2") (pintype "passive"))
      (node (ref "R13") (pin "1") (pinfunction "1_1") (pintype "passive"))
      (node (ref "esp") (pin "5") (pinfunction "22_5") (pintype "bidirectional"))
    )
    (net (code "36") (name "/Touch_14") (class "Default")
      (node (ref "D53") (pin "2") (pinfunction "2_2") (pintype "passive"))
      (node (ref "D54") (pin "2") (pinfunction "2_2") (pintype "passive"))
      (node (ref "D55") (pin "2") (pinfunction "2_2") (pintype "passive"))
      (node (ref "D56") (pin "2") (pinfunction "2_2") (pintype "passive"))
      (node (ref "R14") (pin "1") (pinfunction "1_1") (pintype "passive"))
      (node (ref "esp") (pin "9") (pinfunction "19_9") (pintype "bidirectional"))
    )
    (net (code "37") (name "/Touch_15") (class "Default")
      (node (ref "D57") (pin "2") (pinfunction "2_2") (pintype "passive"))
      (node (ref "D58") (pin "2") (pinfunction "2_2") (pintype "passive"))
      (node (ref "D59") (pin "2") (pinfunction "2_2") (pintype "passive"))
      (node (ref "D60") (pin "2") (pinfunction "2_2") (pintype "passive"))
      (node (ref "R15") (pin "1") (pinfunction "1_1") (pintype "passive"))
      (node (ref "esp") (pin "16") (pinfunction "4_16") (pintype "bidirectional"))
    )
    (net (code "38") (name "GND") (class "Default")
      (node (ref "AY1") (pin "3") (pinfunction "VSS_3") (pintype "power_in"))
      (node (ref "AY10") (pin "3") (pinfunction "VSS_3") (pintype "power_in"))
      (node (ref "AY11") (pin "3") (pinfunction "VSS_3") (pintype "power_in"))
      (node (ref "AY12") (pin "3") (pinfunction "VSS_3") (pintype "power_in"))
      (node (ref "AY13") (pin "3") (pinfunction "VSS_3") (pintype "power_in"))
      (node (ref "AY14") (pin "3") (pinfunction "VSS_3") (pintype "power_in"))
      (node (ref "AY15") (pin "3") (pinfunction "VSS_3") (pintype "power_in"))
      (node (ref "AY16") (pin "3") (pinfunction "VSS_3") (pintype "power_in"))
      (node (ref "AY17") (pin "3") (pinfunction "VSS_3") (pintype "power_in"))
      (node (ref "AY18") (pin "3") (pinfunction "VSS_3") (pintype "power_in"))
      (node (ref "AY19") (pin "3") (pinfunction "VSS_3") (pintype "power_in"))
      (node (ref "AY2") (pin "3") (pinfunction "VSS_3") (pintype "power_in"))
      (node (ref "AY20") (pin "3") (pinfunction "VSS_3") (pintype "power_in"))
      (node (ref "AY21") (pin "3") (pinfunction "VSS_3") (pintype "power_in"))
      (node (ref "AY22") (pin "3") (pinfunction "VSS_3") (pintype "power_in"))
      (node (ref "AY23") (pin "3") (pinfunction "VSS_3") (pintype "power_in"))
      (node (ref "AY24") (pin "3") (pinfunction "VSS_3") (pintype "power_in"))
      (node (ref "AY25") (pin "3") (pinfunction "VSS_3") (pintype "power_in"))
      (node (ref "AY26") (pin "3") (pinfunction "VSS_3") (pintype "power_in"))
      (node (ref "AY27") (pin "3") (pinfunction "VSS_3") (pintype "power_in"))
      (node (ref "AY28") (pin "3") (pinfunction "VSS_3") (pintype "power_in"))
      (node (ref "AY29") (pin "3") (pinfunction "VSS_3") (pintype "power_in"))
      (node (ref "AY3") (pin "3") (pinfunction "VSS_3") (pintype "power_in"))
      (node (ref "AY30") (pin "3") (pinfunction "VSS_3") (pintype "power_in"))
      (node (ref "AY31") (pin "3") (pinfunction "VSS_3") (pintype "power_in"))
      (node (ref "AY32") (pin "3") (pinfunction "VSS_3") (pintype "power_in"))
      (node (ref "AY33") (pin "3") (pinfunction "VSS_3") (pintype "power_in"))
      (node (ref "AY34") (pin "3") (pinfunction "VSS_3") (pintype "power_in"))
      (node (ref "AY4") (pin "3") (pinfunction "VSS_3") (pintype "power_in"))
      (node (ref "AY5") (pin "3") (pinfunction "VSS_3") (pintype "power_in"))
      (node (ref "AY6") (pin "3") (pinfunction "VSS_3") (pintype "power_in"))
      (node (ref "AY7") (pin "3") (pinfunction "VSS_3") (pintype "power_in"))
      (node (ref "AY8") (pin "3") (pinfunction "VSS_3") (pintype "power_in"))
      (node (ref "AY9") (pin "3") (pinfunction "VSS_3") (pintype "power_in"))
      (node (ref "Ayo1") (pin "3") (pinfunction "VSS_3") (pintype "power_in"))
      (node (ref "Ayo10") (pin "3") (pinfunction "VSS_3") (pintype "power_in"))
      (node (ref "Ayo11") (pin "3") (pinfunction "VSS_3") (pintype "power_in"))
      (node (ref "Ayo12") (pin "3") (pinfunction "VSS_3") (pintype "power_in"))
      (node (ref "Ayo13") (pin "3") (pinfunction "VSS_3") (pintype "power_in"))
      (node (ref "Ayo14") (pin "3") (pinfunction "VSS_3") (pintype "power_in"))
      (node (ref "Ayo15") (pin "3") (pinfunction "VSS_3") (pintype "power_in"))
      (node (ref "Ayo16") (pin "3") (pinfunction "VSS_3") (pintype "power_in"))
      (node (ref "Ayo17") (pin "3") (pinfunction "VSS_3") (pintype "power_in"))
      (node (ref "Ayo18") (pin "3") (pinfunction "VSS_3") (pintype "power_in"))
      (node (ref "Ayo19") (pin "3") (pinfunction "VSS_3") (pintype "power_in"))
      (node (ref "Ayo2") (pin "3") (pinfunction "VSS_3") (pintype "power_in"))
      (node (ref "Ayo20") (pin "3") (pinfunction "VSS_3") (pintype "power_in"))
      (node (ref "Ayo21") (pin "3") (pinfunction "VSS_3") (pintype "power_in"))
      (node (ref "Ayo22") (pin "3") (pinfunction "VSS_3") (pintype "power_in"))
      (node (ref "Ayo23") (pin "3") (pinfunction "VSS_3") (pintype "power_in"))
      (node (ref "Ayo24") (pin "3") (pinfunction "VSS_3") (pintype "power_in"))
      (node (ref "Ayo25") (pin "3") (pinfunction "VSS_3") (pintype "power_in"))
      (node (ref "Ayo3") (pin "3") (pinfunction "VSS_3") (pintype "power_in"))
      (node (ref "Ayo4") (pin "3") (pinfunction "VSS_3") (pintype "power_in"))
      (node (ref "Ayo5") (pin "3") (pinfunction "VSS_3") (pintype "power_in"))
      (node (ref "Ayo6") (pin "3") (pinfunction "VSS_3") (pintype "power_in"))
      (node (ref "Ayo7") (pin "3") (pinfunction "VSS_3") (pintype "power_in"))
      (node (ref "Ayo8") (pin "3") (pinfunction "VSS_3") (pintype "power_in"))
      (node (ref "Ayo9") (pin "3") (pinfunction "VSS_3") (pintype "power_in"))
      (node (ref "C1") (pin "7") (pinfunction "Gnd_7") (pintype "passive"))
      (node (ref "C2") (pin "1") (pinfunction "-_1") (pintype "passive"))
      (node (ref "C3") (pin "1") (pinfunction "-_1") (pintype "passive"))
      (node (ref "C4") (pin "1") (pinfunction "-_1") (pintype "passive"))
      (node (ref "C5") (pin "1") (pinfunction "-_1") (pintype "passive"))
      (node (ref "C6") (pin "1") (pinfunction "-_1") (pintype "passive"))
      (node (ref "C7") (pin "1") (pinfunction "-_1") (pintype "passive"))
      (node (ref "C8") (pin "1") (pinfunction "-_1") (pintype "passive"))
      (node (ref "D62") (pin "1") (pinfunction "+_1") (pintype "passive"))
      (node (ref "J2") (pin "1") (pinfunction "GND_1") (pintype "power_in"))
      (node (ref "J2") (pin "2") (pinfunction "GND_2") (pintype "passive"))
      (node (ref "J2") (pin "3") (pinfunction "GND_3") (pintype "power_in"))
      (node (ref "R16") (pin "1") (pinfunction "1_1") (pintype "passive"))
      (node (ref "R18") (pin "1") (pinfunction "1_1") (pintype "passive"))
      (node (ref "R20") (pin "1") (pinfunction "1_1") (pintype "passive"))
      (node (ref "R21") (pin "1") (pinfunction "1_1") (pintype "passive"))
      (node (ref "R22") (pin "1") (pinfunction "1_1") (pintype "passive"))
      (node (ref "Relay1") (pin "2") (pinfunction "Coli_B_2") (pintype "passive"))
      (node (ref "T1") (pin "11") (pinfunction "GND_11") (pintype "passive"))
      (node (ref "T1") (pin "2") (pinfunction "GND_2") (pintype "passive"))
      (node (ref "T1") (pin "5") (pinfunction "GND_5") (pintype "passive"))
      (node (ref "T1") (pin "8") (pinfunction "GND_8") (pintype "passive"))
      (node (ref "T10") (pin "11") (pinfunction "GND_11") (pintype "passive"))
      (node (ref "T10") (pin "2") (pinfunction "GND_2") (pintype "passive"))
      (node (ref "T10") (pin "5") (pinfunction "GND_5") (pintype "passive"))
      (node (ref "T10") (pin "8") (pinfunction "GND_8") (pintype "passive"))
      (node (ref "T11") (pin "11") (pinfunction "GND_11") (pintype "passive"))
      (node (ref "T11") (pin "2") (pinfunction "GND_2") (pintype "passive"))
      (node (ref "T11") (pin "5") (pinfunction "GND_5") (pintype "passive"))
      (node (ref "T11") (pin "8") (pinfunction "GND_8") (pintype "passive"))
      (node (ref "T12") (pin "11") (pinfunction "GND_11") (pintype "passive"))
      (node (ref "T12") (pin "2") (pinfunction "GND_2") (pintype "passive"))
      (node (ref "T12") (pin "5") (pinfunction "GND_5") (pintype "passive"))
      (node (ref "T12") (pin "8") (pinfunction "GND_8") (pintype "passive"))
      (node (ref "T13") (pin "11") (pinfunction "GND_11") (pintype "passive"))
      (node (ref "T13") (pin "2") (pinfunction "GND_2") (pintype "passive"))
      (node (ref "T13") (pin "5") (pinfunction "GND_5") (pintype "passive"))
      (node (ref "T13") (pin "8") (pinfunction "GND_8") (pintype "passive"))
      (node (ref "T14") (pin "11") (pinfunction "GND_11") (pintype "passive"))
      (node (ref "T14") (pin "2") (pinfunction "GND_2") (pintype "passive"))
      (node (ref "T14") (pin "5") (pinfunction "GND_5") (pintype "passive"))
      (node (ref "T14") (pin "8") (pinfunction "GND_8") (pintype "passive"))
      (node (ref "T15") (pin "11") (pinfunction "GND_11") (pintype "passive"))
      (node (ref "T15") (pin "2") (pinfunction "GND_2") (pintype "passive"))
      (node (ref "T15") (pin "5") (pinfunction "GND_5") (pintype "passive"))
      (node (ref "T15") (pin "8") (pinfunction "GND_8") (pintype "passive"))
      (node (ref "T2") (pin "11") (pinfunction "GND_11") (pintype "passive"))
      (node (ref "T2") (pin "2") (pinfunction "GND_2") (pintype "passive"))
      (node (ref "T2") (pin "5") (pinfunction "GND_5") (pintype "passive"))
      (node (ref "T2") (pin "8") (pinfunction "GND_8") (pintype "passive"))
      (node (ref "T3") (pin "11") (pinfunction "GND_11") (pintype "passive"))
      (node (ref "T3") (pin "2") (pinfunction "GND_2") (pintype "passive"))
      (node (ref "T3") (pin "5") (pinfunction "GND_5") (pintype "passive"))
      (node (ref "T3") (pin "8") (pinfunction "GND_8") (pintype "passive"))
      (node (ref "T4") (pin "11") (pinfunction "GND_11") (pintype "passive"))
      (node (ref "T4") (pin "2") (pinfunction "GND_2") (pintype "passive"))
      (node (ref "T4") (pin "5") (pinfunction "GND_5") (pintype "passive"))
      (node (ref "T4") (pin "8") (pinfunction "GND_8") (pintype "passive"))
      (node (ref "T5") (pin "11") (pinfunction "GND_11") (pintype "passive"))
      (node (ref "T5") (pin "2") (pinfunction "GND_2") (pintype "passive"))
      (node (ref "T5") (pin "5") (pinfunction "GND_5") (pintype "passive"))
      (node (ref "T5") (pin "8") (pinfunction "GND_8") (pintype "passive"))
      (node (ref "T6") (pin "11") (pinfunction "GND_11") (pintype "passive"))
      (node (ref "T6") (pin "2") (pinfunction "GND_2") (pintype "passive"))
      (node (ref "T6") (pin "5") (pinfunction "GND_5") (pintype "passive"))
      (node (ref "T6") (pin "8") (pinfunction "GND_8") (pintype "passive"))
      (node (ref "T7") (pin "11") (pinfunction "GND_11") (pintype "passive"))
      (node (ref "T7") (pin "2") (pinfunction "GND_2") (pintype "passive"))
      (node (ref "T7") (pin "5") (pinfunction "GND_5") (pintype "passive"))
      (node (ref "T7") (pin "8") (pinfunction "GND_8") (pintype "passive"))
      (node (ref "T8") (pin "11") (pinfunction "GND_11") (pintype "passive"))
      (node (ref "T8") (pin "2") (pinfunction "GND_2") (pintype "passive"))
      (node (ref "T8") (pin "5") (pinfunction "GND_5") (pintype "passive"))
      (node (ref "T8") (pin "8") (pinfunction "GND_8") (pintype "passive"))
      (node (ref "T9") (pin "11") (pinfunction "GND_11") (pintype "passive"))
      (node (ref "T9") (pin "2") (pinfunction "GND_2") (pintype "passive"))
      (node (ref "T9") (pin "5") (pinfunction "GND_5") (pintype "passive"))
      (node (ref "T9") (pin "8") (pinfunction "GND_8") (pintype "passive"))
      (node (ref "cp1") (pin "29") (pinfunction "GND_29") (pintype "passive"))
      (node (ref "cp1") (pin "3") (pinfunction "GND_3") (pintype "passive"))
      (node (ref "esp") (pin "1") (pinfunction "GND_1") (pintype "power_in"))
      (node (ref "esp") (pin "18") (pinfunction "GND_18") (pintype "power_in"))
      (node (ref "esp") (pin "36") (pinfunction "GND_36") (pintype "power_in"))
      (node (ref "esp") (pin "7") (pinfunction "GND_7") (pintype "power_in"))
      (node (ref "esp") (pin "8") (pinfunction "GND_8") (pintype "power_in"))
      (node (ref "usb1") (pin "1") (pinfunction "GND_1") (pintype "power_in"))
    )
    (net (code "39") (name "Group_A_+5V") (class "Default")
      (node (ref "AY1") (pin "1") (pinfunction "VDD_1") (pintype "power_in"))
      (node (ref "AY2") (pin "1") (pinfunction "VDD_1") (pintype "power_in"))
      (node (ref "AY3") (pin "1") (pinfunction "VDD_1") (pintype "power_in"))
      (node (ref "AY4") (pin "1") (pinfunction "VDD_1") (pintype "power_in"))
      (node (ref "AY5") (pin "1") (pinfunction "VDD_1") (pintype "power_in"))
      (node (ref "AY6") (pin "1") (pinfunction "VDD_1") (pintype "power_in"))
      (node (ref "AY7") (pin "1") (pinfunction "VDD_1") (pintype "power_in"))
      (node (ref "AY8") (pin "1") (pinfunction "VDD_1") (pintype "power_in"))
      (node (ref "AY9") (pin "1") (pinfunction "VDD_1") (pintype "power_in"))
      (node (ref "F1") (pin "2") (pinfunction "2_2") (pintype "passive"))
    )
    (net (code "40") (name "Group_B_+5V") (class "Default")
      (node (ref "AY10") (pin "1") (pinfunction "VDD_1") (pintype "power_in"))
      (node (ref "AY11") (pin "1") (pinfunction "VDD_1") (pintype "power_in"))
      (node (ref "AY12") (pin "1") (pinfunction "VDD_1") (pintype "power_in"))
      (node (ref "AY13") (pin "1") (pinfunction "VDD_1") (pintype "power_in"))
      (node (ref "AY14") (pin "1") (pinfunction "VDD_1") (pintype "power_in"))
      (node (ref "AY15") (pin "1") (pinfunction "VDD_1") (pintype "power_in"))
      (node (ref "AY16") (pin "1") (pinfunction "VDD_1") (pintype "power_in"))
      (node (ref "AY17") (pin "1") (pinfunction "VDD_1") (pintype "power_in"))
      (node (ref "Ayo1") (pin "1") (pinfunction "VDD_1") (pintype "power_in"))
      (node (ref "Ayo10") (pin "1") (pinfunction "VDD_1") (pintype "power_in"))
      (node (ref "Ayo11") (pin "1") (pinfunction "VDD_1") (pintype "power_in"))
      (node (ref "Ayo12") (pin "1") (pinfunction "VDD_1") (pintype "power_in"))
      (node (ref "Ayo13") (pin "1") (pinfunction "VDD_1") (pintype "power_in"))
      (node (ref "Ayo14") (pin "1") (pinfunction "VDD_1") (pintype "power_in"))
      (node (ref "Ayo15") (pin "1") (pinfunction "VDD_1") (pintype "power_in"))
      (node (ref "Ayo2") (pin "1") (pinfunction "VDD_1") (pintype "power_in"))
      (node (ref "Ayo3") (pin "1") (pinfunction "VDD_1") (pintype "power_in"))
      (node (ref "Ayo4") (pin "1") (pinfunction "VDD_1") (pintype "power_in"))
      (node (ref "Ayo5") (pin "1") (pinfunction "VDD_1") (pintype "power_in"))
      (node (ref "Ayo6") (pin "1") (pinfunction "VDD_1") (pintype "power_in"))
      (node (ref "Ayo7") (pin "1") (pinfunction "VDD_1") (pintype "power_in"))
      (node (ref "Ayo8") (pin "1") (pinfunction "VDD_1") (pintype "power_in"))
      (node (ref "Ayo9") (pin "1") (pinfunction "VDD_1") (pintype "power_in"))
      (node (ref "F2") (pin "2") (pinfunction "2_2") (pintype "passive"))
    )
    (net (code "41") (name "Group_C_+5V") (class "Default")
      (node (ref "AY18") (pin "1") (pinfunction "VDD_1") (pintype "power_in"))
      (node (ref "AY19") (pin "1") (pinfunction "VDD_1") (pintype "power_in"))
      (node (ref "AY20") (pin "1") (pinfunction "VDD_1") (pintype "power_in"))
      (node (ref "AY21") (pin "1") (pinfunction "VDD_1") (pintype "power_in"))
      (node (ref "AY22") (pin "1") (pinfunction "VDD_1") (pintype "power_in"))
      (node (ref "AY23") (pin "1") (pinfunction "VDD_1") (pintype "power_in"))
      (node (ref "AY24") (pin "1") (pinfunction "VDD_1") (pintype "power_in"))
      (node (ref "AY25") (pin "1") (pinfunction "VDD_1") (pintype "power_in"))
      (node (ref "Ayo16") (pin "1") (pinfunction "VDD_1") (pintype "power_in"))
      (node (ref "Ayo17") (pin "1") (pinfunction "VDD_1") (pintype "power_in"))
      (node (ref "Ayo18") (pin "1") (pinfunction "VDD_1") (pintype "power_in"))
      (node (ref "Ayo19") (pin "1") (pinfunction "VDD_1") (pintype "power_in"))
      (node (ref "Ayo20") (pin "1") (pinfunction "VDD_1") (pintype "power_in"))
      (node (ref "Ayo21") (pin "1") (pinfunction "VDD_1") (pintype "power_in"))
      (node (ref "Ayo22") (pin "1") (pinfunction "VDD_1") (pintype "power_in"))
      (node (ref "Ayo23") (pin "1") (pinfunction "VDD_1") (pintype "power_in"))
      (node (ref "Ayo24") (pin "1") (pinfunction "VDD_1") (pintype "power_in"))
      (node (ref "Ayo25") (pin "1") (pinfunction "VDD_1") (pintype "power_in"))
      (node (ref "F3") (pin "2") (pinfunction "2_2") (pintype "passive"))
    )
    (net (code "42") (name "Group_D_+5V") (class "Default")
      (node (ref "AY26") (pin "1") (pinfunction "VDD_1") (pintype "power_in"))
      (node (ref "AY27") (pin "1") (pinfunction "VDD_1") (pintype "power_in"))
      (node (ref "AY28") (pin "1") (pinfunction "VDD_1") (pintype "power_in"))
      (node (ref "AY29") (pin "1") (pinfunction "VDD_1") (pintype "power_in"))
      (node (ref "AY30") (pin "1") (pinfunction "VDD_1") (pintype "power_in"))
      (node (ref "AY31") (pin "1") (pinfunction "VDD_1") (pintype "power_in"))
      (node (ref "AY32") (pin "1") (pinfunction "VDD_1") (pintype "power_in"))
      (node (ref "AY33") (pin "1") (pinfunction "VDD_1") (pintype "power_in"))
      (node (ref "AY34") (pin "1") (pinfunction "VDD_1") (pintype "power_in"))
      (node (ref "F4") (pin "2") (pinfunction "2_2") (pintype "passive"))
    )
    (net (code "43") (name "Net-(AY1-DOUT)") (class "Default")
      (node (ref "AY1") (pin "2") (pinfunction "DOUT_2") (pintype "passive"))
      (node (ref "AY2") (pin "4") (pinfunction "DIN_4") (pintype "passive"))
    )
    (net (code "44") (name "Net-(AY2-DOUT)") (class "Default")
      (node (ref "AY2") (pin "2") (pinfunction "DOUT_2") (pintype "passive"))
      (node (ref "AY3") (pin "4") (pinfunction "DIN_4") (pintype "passive"))
    )
    (net (code "45") (name "Net-(AY3-DOUT)") (class "Default")
      (node (ref "AY3") (pin "2") (pinfunction "DOUT_2") (pintype "passive"))
      (node (ref "AY4") (pin "4") (pinfunction "DIN_4") (pintype "passive"))
    )
    (net (code "46") (name "Net-(AY4-DOUT)") (class "Default")
      (node (ref "AY4") (pin "2") (pinfunction "DOUT_2") (pintype "passive"))
      (node (ref "AY5") (pin "4") (pinfunction "DIN_4") (pintype "passive"))
    )
    (net (code "47") (name "Net-(AY5-DOUT)") (class "Default")
      (node (ref "AY5") (pin "2") (pinfunction "DOUT_2") (pintype "passive"))
      (node (ref "AY6") (pin "4") (pinfunction "DIN_4") (pintype "passive"))
    )
    (net (code "48") (name "Net-(AY6-DOUT)") (class "Default")
      (node (ref "AY6") (pin "2") (pinfunction "DOUT_2") (pintype "passive"))
      (node (ref "AY7") (pin "4") (pinfunction "DIN_4") (pintype "passive"))
    )
    (net (code "49") (name "Net-(AY7-DOUT)") (class "Default")
      (node (ref "AY7") (pin "2") (pinfunction "DOUT_2") (pintype "passive"))
      (node (ref "AY8") (pin "4") (pinfunction "DIN_4") (pintype "passive"))
    )
    (net (code "50") (name "Net-(AY8-DOUT)") (class "Default")
      (node (ref "AY8") (pin "2") (pinfunction "DOUT_2") (pintype "passive"))
      (node (ref "AY9") (pin "4") (pinfunction "DIN_4") (pintype "passive"))
    )
    (net (code "51") (name "Net-(AY10-DIN)") (class "Default")
      (node (ref "AY10") (pin "4") (pinfunction "DIN_4") (pintype "passive"))
      (node (ref "Ayo5") (pin "2") (pinfunction "DOUT_2") (pintype "passive"))
    )
    (net (code "52") (name "Net-(AY10-DOUT)") (class "Default")
      (node (ref "AY10") (pin "2") (pinfunction "DOUT_2") (pintype "passive"))
      (node (ref "AY11") (pin "4") (pinfunction "DIN_4") (pintype "passive"))
    )
    (net (code "53") (name "Net-(AY11-DOUT)") (class "Default")
      (node (ref "AY11") (pin "2") (pinfunction "DOUT_2") (pintype "passive"))
      (node (ref "AY12") (pin "4") (pinfunction "DIN_4") (pintype "passive"))
    )
    (net (code "54") (name "Net-(AY12-DOUT)") (class "Default")
      (node (ref "AY12") (pin "2") (pinfunction "DOUT_2") (pintype "passive"))
      (node (ref "AY13") (pin "4") (pinfunction "DIN_4") (pintype "passive"))
    )
    (net (code "55") (name "Net-(AY13-DOUT)") (class "Default")
      (node (ref "AY13") (pin "2") (pinfunction "DOUT_2") (pintype "passive"))
      (node (ref "Ayo6") (pin "4") (pinfunction "DIN_4") (pintype "passive"))
    )
    (net (code "56") (name "Net-(AY14-DIN)") (class "Default")
      (node (ref "AY14") (pin "4") (pinfunction "DIN_4") (pintype "passive"))
      (node (ref "Ayo10") (pin "2") (pinfunction "DOUT_2") (pintype "passive"))
    )
    (net (code "57") (name "Net-(AY14-DOUT)") (class "Default")
      (node (ref "AY14") (pin "2") (pinfunction "DOUT_2") (pintype "passive"))
      (node (ref "AY15") (pin "4") (pinfunction "DIN_4") (pintype "passive"))
    )
    (net (code "58") (name "Net-(AY15-DOUT)") (class "Default")
      (node (ref "AY15") (pin "2") (pinfunction "DOUT_2") (pintype "passive"))
      (node (ref "AY16") (pin "4") (pinfunction "DIN_4") (pintype "passive"))
    )
    (net (code "59") (name "Net-(AY16-DOUT)") (class "Default")
      (node (ref "AY16") (pin "2") (pinfunction "DOUT_2") (pintype "passive"))
      (node (ref "AY17") (pin "4") (pinfunction "DIN_4") (pintype "passive"))
    )
    (net (code "60") (name "Net-(AY17-DOUT)") (class "Default")
      (node (ref "AY17") (pin "2") (pinfunction "DOUT_2") (pintype "passive"))
      (node (ref "Ayo11") (pin "4") (pinfunction "DIN_4") (pintype "passive"))
    )
    (net (code "61") (name "Net-(AY18-DOUT)") (class "Default")
      (node (ref "AY18") (pin "2") (pinfunction "DOUT_2") (pintype "passive"))
      (node (ref "AY19") (pin "4") (pinfunction "DIN_4") (pintype "passive"))
    )
    (net (code "62") (name "Net-(AY19-DOUT)") (class "Default")
      (node (ref "AY19") (pin "2") (pinfunction "DOUT_2") (pintype "passive"))
      (node (ref "AY20") (pin "4") (pinfunction "DIN_4") (pintype "passive"))
    )
    (net (code "63") (name "Net-(AY20-DOUT)") (class "Default")
      (node (ref "AY20") (pin "2") (pinfunction "DOUT_2") (pintype "passive"))
      (node (ref "AY21") (pin "4") (pinfunction "DIN_4") (pintype "passive"))
    )
    (net (code "64") (name "Net-(AY21-DOUT)") (class "Default")
      (node (ref "AY21") (pin "2") (pinfunction "DOUT_2") (pintype "passive"))
      (node (ref "Ayo16") (pin "4") (pinfunction "DIN_4") (pintype "passive"))
    )
    (net (code "65") (name "Net-(AY22-DIN)") (class "Default")
      (node (ref "AY22") (pin "4") (pinfunction "DIN_4") (pintype "passive"))
      (node (ref "Ayo20") (pin "2") (pinfunction "DOUT_2") (pintype "passive"))
    )
    (net (code "66") (name "Net-(AY22-DOUT)") (class "Default")
      (node (ref "AY22") (pin "2") (pinfunction "DOUT_2") (pintype "passive"))
      (node (ref "AY23") (pin "4") (pinfunction "DIN_4") (pintype "passive"))
    )
    (net (code "67") (name "Net-(AY23-DOUT)") (class "Default")
      (node (ref "AY23") (pin "2") (pinfunction "DOUT_2") (pintype "passive"))
      (node (ref "AY24") (pin "4") (pinfunction "DIN_4") (pintype "passive"))
    )
    (net (code "68") (name "Net-(AY24-DOUT)") (class "Default")
      (node (ref "AY24") (pin "2") (pinfunction "DOUT_2") (pintype "passive"))
      (node (ref "AY25") (pin "4") (pinfunction "DIN_4") (pintype "passive"))
    )
    (net (code "69") (name "Net-(AY25-DOUT)") (class "Default")
      (node (ref "AY25") (pin "2") (pinfunction "DOUT_2") (pintype "passive"))
      (node (ref "Ayo21") (pin "4") (pinfunction "DIN_4") (pintype "passive"))
    )
    (net (code "70") (name "Net-(AY26-DOUT)") (class "Default")
      (node (ref "AY26") (pin "2") (pinfunction "DOUT_2") (pintype "passive"))
      (node (ref "AY27") (pin "4") (pinfunction "DIN_4") (pintype "passive"))
    )
    (net (code "71") (name "Net-(AY27-DOUT)") (class "Default")
      (node (ref "AY27") (pin "2") (pinfunction "DOUT_2") (pintype "passive"))
      (node (ref "AY28") (pin "4") (pinfunction "DIN_4") (pintype "passive"))
    )
    (net (code "72") (name "Net-(AY28-DOUT)") (class "Default")
      (node (ref "AY28") (pin "2") (pinfunction "DOUT_2") (pintype "passive"))
      (node (ref "AY29") (pin "4") (pinfunction "DIN_4") (pintype "passive"))
    )
    (net (code "73") (name "Net-(AY29-DOUT)") (class "Default")
      (node (ref "AY29") (pin "2") (pinfunction "DOUT_2") (pintype "passive"))
      (node (ref "AY30") (pin "4") (pinfunction "DIN_4") (pintype "passive"))
    )
    (net (code "74") (name "Net-(AY30-DOUT)") (class "Default")
      (node (ref "AY30") (pin "2") (pinfunction "DOUT_2") (pintype "passive"))
      (node (ref "AY31") (pin "4") (pinfunction "DIN_4") (pintype "passive"))
    )
    (net (code "75") (name "Net-(AY31-DOUT)") (class "Default")
      (node (ref "AY31") (pin "2") (pinfunction "DOUT_2") (pintype "passive"))
      (node (ref "AY32") (pin "4") (pinfunction "DIN_4") (pintype "passive"))
    )
    (net (code "76") (name "Net-(AY32-DOUT)") (class "Default")
      (node (ref "AY32") (pin "2") (pinfunction "DOUT_2") (pintype "passive"))
      (node (ref "AY33") (pin "4") (pinfunction "DIN_4") (pintype "passive"))
    )
    (net (code "77") (name "Net-(AY33-DOUT)") (class "Default")
      (node (ref "AY33") (pin "2") (pinfunction "DOUT_2") (pintype "passive"))
      (node (ref "AY34") (pin "4") (pinfunction "DIN_4") (pintype "passive"))
    )
    (net (code "78") (name "Net-(Ayo1-DOUT)") (class "Default")
      (node (ref "Ayo1") (pin "2") (pinfunction "DOUT_2") (pintype "passive"))
      (node (ref "Ayo2") (pin "4") (pinfunction "DIN_4") (pintype "passive"))
    )
    (net (code "79") (name "Net-(Ayo2-DOUT)") (class "Default")
      (node (ref "Ayo2") (pin "2") (pinfunction "DOUT_2") (pintype "passive"))
      (node (ref "Ayo3") (pin "4") (pinfunction "DIN_4") (pintype "passive"))
    )
    (net (code "80") (name "Net-(Ayo3-DOUT)") (class "Default")
      (node (ref "Ayo3") (pin "2") (pinfunction "DOUT_2") (pintype "passive"))
      (node (ref "Ayo4") (pin "4") (pinfunction "DIN_4") (pintype "passive"))
    )
    (net (code "81") (name "Net-(Ayo4-DOUT)") (class "Default")
      (node (ref "Ayo4") (pin "2") (pinfunction "DOUT_2") (pintype "passive"))
      (node (ref "Ayo5") (pin "4") (pinfunction "DIN_4") (pintype "passive"))
    )
    (net (code "82") (name "Net-(Ayo6-DOUT)") (class "Default")
      (node (ref "Ayo6") (pin "2") (pinfunction "DOUT_2") (pintype "passive"))
      (node (ref "Ayo7") (pin "4") (pinfunction "DIN_4") (pintype "passive"))
    )
    (net (code "83") (name "Net-(Ayo7-DOUT)") (class "Default")
      (node (ref "Ayo7") (pin "2") (pinfunction "DOUT_2") (pintype "passive"))
      (node (ref "Ayo8") (pin "4") (pinfunction "DIN_4") (pintype "passive"))
    )
    (net (code "84") (name "Net-(Ayo8-DOUT)") (class "Default")
      (node (ref "Ayo8") (pin "2") (pinfunction "DOUT_2") (pintype "passive"))
      (node (ref "Ayo9") (pin "4") (pinfunction "DIN_4") (pintype "passive"))
    )
    (net (code "85") (name "Net-(Ayo10-DIN)") (class "Default")
      (node (ref "Ayo10") (pin "4") (pinfunction "DIN_4") (pintype "passive"))
      (node (ref "Ayo9") (pin "2") (pinfunction "DOUT_2") (pintype "passive"))
    )
    (net (code "86") (name "Net-(Ayo11-DOUT)") (class "Default")
      (node (ref "Ayo11") (pin "2") (pinfunction "DOUT_2") (pintype "passive"))
      (node (ref "Ayo12") (pin "4") (pinfunction "DIN_4") (pintype "passive"))
    )
    (net (code "87") (name "Net-(Ayo12-DOUT)") (class "Default")
      (node (ref "Ayo12") (pin "2") (pinfunction "DOUT_2") (pintype "passive"))
      (node (ref "Ayo13") (pin "4") (pinfunction "DIN_4") (pintype "passive"))
    )
    (net (code "88") (name "Net-(Ayo13-DOUT)") (class "Default")
      (node (ref "Ayo13") (pin "2") (pinfunction "DOUT_2") (pintype "passive"))
      (node (ref "Ayo14") (pin "4") (pinfunction "DIN_4") (pintype "passive"))
    )
    (net (code "89") (name "Net-(Ayo14-DOUT)") (class "Default")
      (node (ref "Ayo14") (pin "2") (pinfunction "DOUT_2") (pintype "passive"))
      (node (ref "Ayo15") (pin "4") (pinfunction "DIN_4") (pintype "passive"))
    )
    (net (code "90") (name "Net-(Ayo16-DOUT)") (class "Default")
      (node (ref "Ayo16") (pin "2") (pinfunction "DOUT_2") (pintype "passive"))
      (node (ref "Ayo17") (pin "4") (pinfunction "DIN_4") (pintype "passive"))
    )
    (net (code "91") (name "Net-(Ayo17-DOUT)") (class "Default")
      (node (ref "Ayo17") (pin "2") (pinfunction "DOUT_2") (pintype "passive"))
      (node (ref "Ayo18") (pin "4") (pinfunction "DIN_4") (pintype "passive"))
    )
    (net (code "92") (name "Net-(Ayo18-DOUT)") (class "Default")
      (node (ref "Ayo18") (pin "2") (pinfunction "DOUT_2") (pintype "passive"))
      (node (ref "Ayo19") (pin "4") (pinfunction "DIN_4") (pintype "passive"))
    )
    (net (code "93") (name "Net-(Ayo19-DOUT)") (class "Default")
      (node (ref "Ayo19") (pin "2") (pinfunction "DOUT_2") (pintype "passive"))
      (node (ref "Ayo20") (pin "4") (pinfunction "DIN_4") (pintype "passive"))
    )
    (net (code "94") (name "Net-(Ayo21-DOUT)") (class "Default")
      (node (ref "Ayo21") (pin "2") (pinfunction "DOUT_2") (pintype "passive"))
      (node (ref "Ayo22") (pin "4") (pinfunction "DIN_4") (pintype "passive"))
    )
    (net (code "95") (name "Net-(Ayo22-DOUT)") (class "Default")
      (node (ref "Ayo22") (pin "2") (pinfunction "DOUT_2") (pintype "passive"))
      (node (ref "Ayo23") (pin "4") (pinfunction "DIN_4") (pintype "passive"))
    )
    (net (code "96") (name "Net-(Ayo23-DOUT)") (class "Default")
      (node (ref "Ayo23") (pin "2") (pinfunction "DOUT_2") (pintype "passive"))
      (node (ref "Ayo24") (pin "4") (pinfunction "DIN_4") (pintype "passive"))
    )
    (net (code "97") (name "Net-(Ayo24-DOUT)") (class "Default")
      (node (ref "Ayo24") (pin "2") (pinfunction "DOUT_2") (pintype "passive"))
      (node (ref "Ayo25") (pin "4") (pinfunction "DIN_4") (pintype "passive"))
    )
    (net (code "98") (name "Net-(C4-+)") (class "Default")
      (node (ref "C4") (pin "2") (pinfunction "+_2") (pintype "passive"))
      (node (ref "C5") (pin "2") (pinfunction "+_2") (pintype "passive"))
      (node (ref "R19") (pin "1") (pinfunction "1_1") (pintype "passive"))
      (node (ref "cp1") (pin "6") (pinfunction "VDD_6") (pintype "passive"))
    )
    (net (code "99") (name "Net-(D1-Pad1)") (class "Default")
      (node (ref "D1") (pin "1") (pinfunction "1_1") (pintype "passive"))
      (node (ref "T1") (pin "9") (pinfunction "OUT_9") (pintype "passive"))
    )
    (net (code "100") (name "Net-(D2-Pad1)") (class "Default")
      (node (ref "D2") (pin "1") (pinfunction "1_1") (pintype "passive"))
      (node (ref "T1") (pin "12") (pinfunction "OUT_12") (pintype "passive"))
    )
    (net (code "101") (name "Net-(D3-Pad1)") (class "Default")
      (node (ref "D3") (pin "1") (pinfunction "1_1") (pintype "passive"))
      (node (ref "T1") (pin "3") (pinfunction "OUT_3") (pintype "passive"))
    )
    (net (code "102") (name "Net-(D4-Pad1)") (class "Default")
      (node (ref "D4") (pin "1") (pinfunction "1_1") (pintype "passive"))
      (node (ref "T1") (pin "6") (pinfunction "OUT_6") (pintype "passive"))
    )
    (net (code "103") (name "Net-(D5-Pad1)") (class "Default")
      (node (ref "D5") (pin "1") (pinfunction "1_1") (pintype "passive"))
      (node (ref "T2") (pin "9") (pinfunction "OUT_9") (pintype "passive"))
    )
    (net (code "104") (name "Net-(D6-Pad1)") (class "Default")
      (node (ref "D6") (pin "1") (pinfunction "1_1") (pintype "passive"))
      (node (ref "T2") (pin "12") (pinfunction "OUT_12") (pintype "passive"))
    )
    (net (code "105") (name "Net-(D7-Pad1)") (class "Default")
      (node (ref "D7") (pin "1") (pinfunction "1_1") (pintype "passive"))
      (node (ref "T2") (pin "3") (pinfunction "OUT_3") (pintype "passive"))
    )
    (net (code "106") (name "Net-(D8-Pad1)") (class "Default")
      (node (ref "D8") (pin "1") (pinfunction "1_1") (pintype "passive"))
      (node (ref "T2") (pin "6") (pinfunction "OUT_6") (pintype "passive"))
    )
    (net (code "107") (name "Net-(D9-Pad1)") (class "Default")
      (node (ref "D9") (pin "1") (pinfunction "1_1") (pintype "passive"))
      (node (ref "T3") (pin "9") (pinfunction "OUT_9") (pintype "passive"))
    )
    (net (code "108") (name "Net-(D10-Pad1)") (class "Default")
      (node (ref "D10") (pin "1") (pinfunction "1_1") (pintype "passive"))
      (node (ref "T3") (pin "12") (pinfunction "OUT_12") (pintype "passive"))
    )
    (net (code "109") (name "Net-(D11-Pad1)") (class "Default")
      (node (ref "D11") (pin "1") (pinfunction "1_1") (pintype "passive"))
      (node (ref "T3") (pin "3") (pinfunction "OUT_3") (pintype "passive"))
    )
    (net (code "110") (name "Net-(D12-Pad1)") (class "Default")
      (node (ref "D12") (pin "1") (pinfunction "1_1") (pintype "passive"))
      (node (ref "T3") (pin "6") (pinfunction "OUT_6") (pintype "passive"))
    )
    (net (code "111") (name "Net-(D13-Pad1)") (class "Default")
      (node (ref "D13") (pin "1") (pinfunction "1_1") (pintype "passive"))
      (node (ref "T4") (pin "9") (pinfunction "OUT_9") (pintype "passive"))
    )
    (net (code "112") (name "Net-(D14-Pad1)") (class "Default")
      (node (ref "D14") (pin "1") (pinfunction "1_1") (pintype "passive"))
      (node (ref "T4") (pin "12") (pinfunction "OUT_12") (pintype "passive"))
    )
    (net (code "113") (name "Net-(D15-Pad1)") (class "Default")
      (node (ref "D15") (pin "1") (pinfunction "1_1") (pintype "passive"))
      (node (ref "T4") (pin "3") (pinfunction "OUT_3") (pintype "passive"))
    )
    (net (code "114") (name "Net-(D16-Pad1)") (class "Default")
      (node (ref "D16") (pin "1") (pinfunction "1_1") (pintype "passive"))
      (node (ref "T4") (pin "6") (pinfunction "OUT_6") (pintype "passive"))
    )
    (net (code "115") (name "Net-(D17-Pad1)") (class "Default")
      (node (ref "D17") (pin "1") (pinfunction "1_1") (pintype "passive"))
      (node (ref "T5") (pin "9") (pinfunction "OUT_9") (pintype "passive"))
    )
    (net (code "116") (name "Net-(D18-Pad1)") (class "Default")
      (node (ref "D18") (pin "1") (pinfunction "1_1") (pintype "passive"))
      (node (ref "T5") (pin "12") (pinfunction "OUT_12") (pintype "passive"))
    )
    (net (code "117") (name "Net-(D19-Pad1)") (class "Default")
      (node (ref "D19") (pin "1") (pinfunction "1_1") (pintype "passive"))
      (node (ref "T5") (pin "3") (pinfunction "OUT_3") (pintype "passive"))
    )
    (net (code "118") (name "Net-(D20-Pad1)") (class "Default")
      (node (ref "D20") (pin "1") (pinfunction "1_1") (pintype "passive"))
      (node (ref "T5") (pin "6") (pinfunction "OUT_6") (pintype "passive"))
    )
    (net (code "119") (name "Net-(D21-Pad1)") (class "Default")
      (node (ref "D21") (pin "1") (pinfunction "1_1") (pintype "passive"))
      (node (ref "T6") (pin "9") (pinfunction "OUT_9") (pintype "passive"))
    )
    (net (code "120") (name "Net-(D22-Pad1)") (class "Default")
      (node (ref "D22") (pin "1") (pinfunction "1_1") (pintype "passive"))
      (node (ref "T6") (pin "12") (pinfunction "OUT_12") (pintype "passive"))
    )
    (net (code "121") (name "Net-(D23-Pad1)") (class "Default")
      (node (ref "D23") (pin "1") (pinfunction "1_1") (pintype "passive"))
      (node (ref "T6") (pin "3") (pinfunction "OUT_3") (pintype "passive"))
    )
    (net (code "122") (name "Net-(D24-Pad1)") (class "Default")
      (node (ref "D24") (pin "1") (pinfunction "1_1") (pintype "passive"))
      (node (ref "T6") (pin "6") (pinfunction "OUT_6") (pintype "passive"))
    )
    (net (code "123") (name "Net-(D25-Pad1)") (class "Default")
      (node (ref "D25") (pin "1") (pinfunction "1_1") (pintype "passive"))
      (node (ref "T7") (pin "9") (pinfunction "OUT_9") (pintype "passive"))
    )
    (net (code "124") (name "Net-(D26-Pad1)") (class "Default")
      (node (ref "D26") (pin "1") (pinfunction "1_1") (pintype "passive"))
      (node (ref "T7") (pin "12") (pinfunction "OUT_12") (pintype "passive"))
    )
    (net (code "125") (name "Net-(D27-Pad1)") (class "Default")
      (node (ref "D27") (pin "1") (pinfunction "1_1") (pintype "passive"))
      (node (ref "T7") (pin "3") (pinfunction "OUT_3") (pintype "passive"))
    )
    (net (code "126") (name "Net-(D28-Pad1)") (class "Default")
      (node (ref "D28") (pin "1") (pinfunction "1_1") (pintype "passive"))
      (node (ref "T7") (pin "6") (pinfunction "OUT_6") (pintype "passive"))
    )
    (net (code "127") (name "Net-(D29-Pad1)") (class "Default")
      (node (ref "D29") (pin "1") (pinfunction "1_1") (pintype "passive"))
      (node (ref "T8") (pin "9") (pinfunction "OUT_9") (pintype "passive"))
    )
    (net (code "128") (name "Net-(D30-Pad1)") (class "Default")
      (node (ref "D30") (pin "1") (pinfunction "1_1") (pintype "passive"))
      (node (ref "T8") (pin "12") (pinfunction "OUT_12") (pintype "passive"))
    )
    (net (code "129") (name "Net-(D31-Pad1)") (class "Default")
      (node (ref "D31") (pin "1") (pinfunction "1_1") (pintype "passive"))
      (node (ref "T8") (pin "3") (pinfunction "OUT_3") (pintype "passive"))
    )
    (net (code "130") (name "Net-(D32-Pad1)") (class "Default")
      (node (ref "D32") (pin "1") (pinfunction "1_1") (pintype "passive"))
      (node (ref "T8") (pin "6") (pinfunction "OUT_6") (pintype "passive"))
    )
    (net (code "131") (name "Net-(D33-Pad1)") (class "Default")
      (node (ref "D33") (pin "1") (pinfunction "1_1") (pintype "passive"))
      (node (ref "T9") (pin "9") (pinfunction "OUT_9") (pintype "passive"))
    )
    (net (code "132") (name "Net-(D34-Pad1)") (class "Default")
      (node (ref "D34") (pin "1") (pinfunction "1_1") (pintype "passive"))
      (node (ref "T9") (pin "12") (pinfunction "OUT_12") (pintype "passive"))
    )
    (net (code "133") (name "Net-(D35-Pad1)") (class "Default")
      (node (ref "D35") (pin "1") (pinfunction "1_1") (pintype "passive"))
      (node (ref "T9") (pin "3") (pinfunction "OUT_3") (pintype "passive"))
    )
    (net (code "134") (name "Net-(D36-Pad1)") (class "Default")
      (node (ref "D36") (pin "1") (pinfunction "1_1") (pintype "passive"))
      (node (ref "T9") (pin "6") (pinfunction "OUT_6") (pintype "passive"))
    )
    (net (code "135") (name "Net-(D37-Pad1)") (class "Default")
      (node (ref "D37") (pin "1") (pinfunction "1_1") (pintype "passive"))
      (node (ref "T10") (pin "9") (pinfunction "OUT_9") (pintype "passive"))
    )
    (net (code "136") (name "Net-(D38-Pad1)") (class "Default")
      (node (ref "D38") (pin "1") (pinfunction "1_1") (pintype "passive"))
      (node (ref "T10") (pin "12") (pinfunction "OUT_12") (pintype "passive"))
    )
    (net (code "137") (name "Net-(D39-Pad1)") (class "Default")
      (node (ref "D39") (pin "1") (pinfunction "1_1") (pintype "passive"))
      (node (ref "T10") (pin "3") (pinfunction "OUT_3") (pintype "passive"))
    )
    (net (code "138") (name "Net-(D40-Pad1)") (class "Default")
      (node (ref "D40") (pin "1") (pinfunction "1_1") (pintype "passive"))
      (node (ref "T10") (pin "6") (pinfunction "OUT_6") (pintype "passive"))
    )
    (net (code "139") (name "Net-(D41-Pad1)") (class "Default")
      (node (ref "D41") (pin "1") (pinfunction "1_1") (pintype "passive"))
      (node (ref "T11") (pin "9") (pinfunction "OUT_9") (pintype "passive"))
    )
    (net (code "140") (name "Net-(D42-Pad1)") (class "Default")
      (node (ref "D42") (pin "1") (pinfunction "1_1") (pintype "passive"))
      (node (ref "T11") (pin "12") (pinfunction "OUT_12") (pintype "passive"))
    )
    (net (code "141") (name "Net-(D43-Pad1)") (class "Default")
      (node (ref "D43") (pin "1") (pinfunction "1_1") (pintype "passive"))
      (node (ref "T11") (pin "3") (pinfunction "OUT_3") (pintype "passive"))
    )
    (net (code "142") (name "Net-(D44-Pad1)") (class "Default")
      (node (ref "D44") (pin "1") (pinfunction "1_1") (pintype "passive"))
      (node (ref "T11") (pin "6") (pinfunction "OUT_6") (pintype "passive"))
    )
    (net (code "143") (name "Net-(D45-Pad1)") (class "Default")
      (node (ref "D45") (pin "1") (pinfunction "1_1") (pintype "passive"))
      (node (ref "T12") (pin "9") (pinfunction "OUT_9") (pintype "passive"))
    )
    (net (code "144") (name "Net-(D46-Pad1)") (class "Default")
      (node (ref "D46") (pin "1") (pinfunction "1_1") (pintype "passive"))
      (node (ref "T12") (pin "12") (pinfunction "OUT_12") (pintype "passive"))
    )
    (net (code "145") (name "Net-(D47-Pad1)") (class "Default")
      (node (ref "D47") (pin "1") (pinfunction "1_1") (pintype "passive"))
      (node (ref "T12") (pin "3") (pinfunction "OUT_3") (pintype "passive"))
    )
    (net (code "146") (name "Net-(D48-Pad1)") (class "Default")
      (node (ref "D48") (pin "1") (pinfunction "1_1") (pintype "passive"))
      (node (ref "T12") (pin "6") (pinfunction "OUT_6") (pintype "passive"))
    )
    (net (code "147") (name "Net-(D49-Pad1)") (class "Default")
      (node (ref "D49") (pin "1") (pinfunction "1_1") (pintype "passive"))
      (node (ref "T13") (pin "9") (pinfunction "OUT_9") (pintype "passive"))
    )
    (net (code "148") (name "Net-(D50-Pad1)") (class "Default")
      (node (ref "D50") (pin "1") (pinfunction "1_1") (pintype "passive"))
      (node (ref "T13") (pin "12") (pinfunction "OUT_12") (pintype "passive"))
    )
    (net (code "149") (name "Net-(D51-Pad1)") (class "Default")
      (node (ref "D51") (pin "1") (pinfunction "1_1") (pintype "passive"))
      (node (ref "T13") (pin "3") (pinfunction "OUT_3") (pintype "passive"))
    )
    (net (code "150") (name "Net-(D52-Pad1)") (class "Default")
      (node (ref "D52") (pin "1") (pinfunction "1_1") (pintype "passive"))
      (node (ref "T13") (pin "6") (pinfunction "OUT_6") (pintype "passive"))
    )
    (net (code "151") (name "Net-(D53-Pad1)") (class "Default")
      (node (ref "D53") (pin "1") (pinfunction "1_1") (pintype "passive"))
      (node (ref "T14") (pin "9") (pinfunction "OUT_9") (pintype "passive"))
    )
    (net (code "152") (name "Net-(D54-Pad1)") (class "Default")
      (node (ref "D54") (pin "1") (pinfunction "1_1") (pintype "passive"))
      (node (ref "T14") (pin "12") (pinfunction "OUT_12") (pintype "passive"))
    )
    (net (code "153") (name "Net-(D55-Pad1)") (class "Default")
      (node (ref "D55") (pin "1") (pinfunction "1_1") (pintype "passive"))
      (node (ref "T14") (pin "3") (pinfunction "OUT_3") (pintype "passive"))
    )
    (net (code "154") (name "Net-(D56-Pad1)") (class "Default")
      (node (ref "D56") (pin "1") (pinfunction "1_1") (pintype "passive"))
      (node (ref "T14") (pin "6") (pinfunction "OUT_6") (pintype "passive"))
    )
    (net (code "155") (name "Net-(D57-Pad1)") (class "Default")
      (node (ref "D57") (pin "1") (pinfunction "1_1") (pintype "passive"))
      (node (ref "T15") (pin "9") (pinfunction "OUT_9") (pintype "passive"))
    )
    (net (code "156") (name "Net-(D58-Pad1)") (class "Default")
      (node (ref "D58") (pin "1") (pinfunction "1_1") (pintype "passive"))
      (node (ref "T15") (pin "12") (pinfunction "OUT_12") (pintype "passive"))
    )
    (net (code "157") (name "Net-(D59-Pad1)") (class "Default")
      (node (ref "D59") (pin "1") (pinfunction "1_1") (pintype "passive"))
      (node (ref "T15") (pin "3") (pinfunction "OUT_3") (pintype "passive"))
    )
    (net (code "158") (name "Net-(D60-Pad1)") (class "Default")
      (node (ref "D60") (pin "1") (pinfunction "1_1") (pintype "passive"))
      (node (ref "T15") (pin "6") (pinfunction "OUT_6") (pintype "passive"))
    )
    (net (code "159") (name "Net-(D61-Pad1)") (class "Default")
      (node (ref "D61") (pin "1") (pinfunction "1_1") (pintype "passive"))
      (node (ref "R16") (pin "2") (pinfunction "2_2") (pintype "passive"))
    )
    (net (code "160") (name "Net-(D63-Pad1)") (class "Default")
      (node (ref "D63") (pin "1") (pinfunction "1_1") (pintype "passive"))
      (node (ref "R20") (pin "2") (pinfunction "2_2") (pintype "passive"))
    )
    (net (code "161") (name "Net-(D63-Pad2)") (class "Default")
      (node (ref "D63") (pin "2") (pinfunction "2_2") (pintype "passive"))
      (node (ref "esp") (pin "4") (pinfunction "3v3_4") (pintype "power_in"))
    )
    (net (code "162") (name "Net-(D64-Pad1)") (class "Default")
      (node (ref "D64") (pin "1") (pinfunction "1_1") (pintype "passive"))
      (node (ref "R22") (pin "2") (pinfunction "2_2") (pintype "passive"))
    )
    (net (code "163") (name "Net-(D65-Pad1)") (class "Default")
      (node (ref "D65") (pin "1") (pinfunction "1_1") (pintype "passive"))
      (node (ref "R21") (pin "2") (pinfunction "2_2") (pintype "passive"))
    )
    (net (code "164") (name "Net-(cp1-D+)") (class "Default")
      (node (ref "D62") (pin "2") (pinfunction "2_2") (pintype "passive"))
      (node (ref "cp1") (pin "4") (pinfunction "D+_4") (pintype "passive"))
      (node (ref "usb1") (pin "2") (pinfunction "DATA+_2") (pintype "bidirectional"))
    )
    (net (code "165") (name "Net-(cp1-D-)") (class "Default")
      (node (ref "D62") (pin "3") (pinfunction "3_3") (pintype "passive"))
      (node (ref "cp1") (pin "5") (pinfunction "D-_5") (pintype "passive"))
      (node (ref "usb1") (pin "3") (pinfunction "DATA-_3") (pintype "bidirectional"))
    )
    (net (code "166") (name "Net-(cp1-RSTb)") (class "Default")
      (node (ref "R19") (pin "2") (pinfunction "2_2") (pintype "passive"))
      (node (ref "cp1") (pin "9") (pinfunction "RSTb_9") (pintype "passive"))
    )
    (net (code "167") (name "Net-(cp1-VBUS)") (class "Default")
      (node (ref "R17") (pin "1") (pinfunction "1_1") (pintype "passive"))
      (node (ref "R18") (pin "2") (pinfunction "2_2") (pintype "passive"))
      (node (ref "cp1") (pin "8") (pinfunction "VBUS_8") (pintype "passive"))
    )
    (net (code "168") (name "USB_5V") (class "Default")
      (node (ref "C2") (pin "2") (pinfunction "+_2") (pintype "passive"))
      (node (ref "C3") (pin "2") (pinfunction "+_2") (pintype "passive"))
      (node (ref "D62") (pin "4") (pinfunction "4_4") (pintype "passive"))
      (node (ref "R17") (pin "2") (pinfunction "2_2") (pintype "passive"))
      (node (ref "Relay1") (pin "4") (pinfunction "NC_4") (pintype "passive"))
      (node (ref "cp1") (pin "7") (pinfunction "VREGIN_7") (pintype "passive"))
      (node (ref "usb1") (pin "4") (pinfunction "5V_4") (pintype "power_in"))
    )
    (net (code "169") (name "unconnected-(cp1-CHR0-Pad15)") (class "Default")
      (node (ref "cp1") (pin "15") (pinfunction "CHR0_15") (pintype "passive"))
    )
    (net (code "170") (name "unconnected-(cp1-CHR1-Pad14)") (class "Default")
      (node (ref "cp1") (pin "14") (pinfunction "CHR1_14") (pintype "passive"))
    )
    (net (code "171") (name "unconnected-(cp1-CHREN-Pad13)") (class "Default")
      (node (ref "cp1") (pin "13") (pinfunction "CHREN_13") (pintype "passive"))
    )
    (net (code "172") (name "unconnected-(cp1-CTS49-Pad23)") (class "Default")
      (node (ref "cp1") (pin "23") (pinfunction "CTS49_23") (pintype "passive"))
    )
    (net (code "173") (name "unconnected-(cp1-DCD-Pad1)") (class "Default")
      (node (ref "cp1") (pin "1") (pinfunction "DCD_1") (pintype "passive"))
    )
    (net (code "174") (name "unconnected-(cp1-DSR-Pad27)") (class "Default")
      (node (ref "cp1") (pin "27") (pinfunction "DSR_27") (pintype "passive"))
    )
    (net (code "175") (name "unconnected-(cp1-IO0{slash}TXT-Pad19)") (class "Default")
      (node (ref "cp1") (pin "19") (pinfunction "IO0/TXT_19") (pintype "passive"))
    )
    (net (code "176") (name "unconnected-(cp1-IO1{slash}RXT-Pad18)") (class "Default")
      (node (ref "cp1") (pin "18") (pinfunction "IO1/RXT_18") (pintype "passive"))
    )
    (net (code "177") (name "unconnected-(cp1-IO2{slash}RS485-Pad17)") (class "Default")
      (node (ref "cp1") (pin "17") (pinfunction "IO2/RS485_17") (pintype "passive"))
    )
    (net (code "178") (name "unconnected-(cp1-IO3{slash}wakeup-Pad16)") (class "Default")
      (node (ref "cp1") (pin "16") (pinfunction "IO3/wakeup_16") (pintype "passive"))
    )
    (net (code "179") (name "unconnected-(cp1-IO4-Pad22)") (class "Default")
      (node (ref "cp1") (pin "22") (pinfunction "IO4_22") (pintype "passive"))
    )
    (net (code "180") (name "unconnected-(cp1-IO5-Pad21)") (class "Default")
      (node (ref "cp1") (pin "21") (pinfunction "IO5_21") (pintype "passive"))
    )
    (net (code "181") (name "unconnected-(cp1-IO6-Pad20)") (class "Default")
      (node (ref "cp1") (pin "20") (pinfunction "IO6_20") (pintype "passive"))
    )
    (net (code "182") (name "unconnected-(cp1-NC-Pad10)") (class "Default")
      (node (ref "cp1") (pin "10") (pinfunction "NC_10") (pintype "passive"))
    )
    (net (code "183") (name "unconnected-(cp1-RI{slash}CLK-Pad2)") (class "Default")
      (node (ref "cp1") (pin "2") (pinfunction "RI/CLK_2") (pintype "passive"))
    )
    (net (code "184") (name "unconnected-(cp1-SUS-Pad12)") (class "Default")
      (node (ref "cp1") (pin "12") (pinfunction "SUS_12") (pintype "passive"))
    )
    (net (code "185") (name "unconnected-(cp1-SUSb-Pad11)") (class "Default")
      (node (ref "cp1") (pin "11") (pinfunction "SUSb_11") (pintype "passive"))
    )
    (net (code "186") (name "unconnected-(esp-3v3-Pad21)") (class "Default")
      (node (ref "esp") (pin "21") (pinfunction "3v3_21") (pintype "power_in"))
    )
    (net (code "187") (name "unconnected-(esp-5V-Pad13)") (class "Default")
      (node (ref "esp") (pin "13") (pinfunction "5V_13") (pintype "power_in"))
    )
    (net (code "188") (name "unconnected-(esp-15-Pad20)") (class "Default")
      (node (ref "esp") (pin "20") (pinfunction "15_20") (pintype "bidirectional"))
    )
    (net (code "189") (name "unconnected-(esp-17-Pad14)") (class "Default")
      (node (ref "esp") (pin "14") (pinfunction "17_14") (pintype "bidirectional"))
    )
    (net (code "190") (name "unconnected-(esp-23-Pad10)") (class "Default")
      (node (ref "esp") (pin "10") (pinfunction "23_10") (pintype "bidirectional"))
    )
  )
)
